# BenchPsu.net
KiCad netlist of a schematic drawn in EAGLE
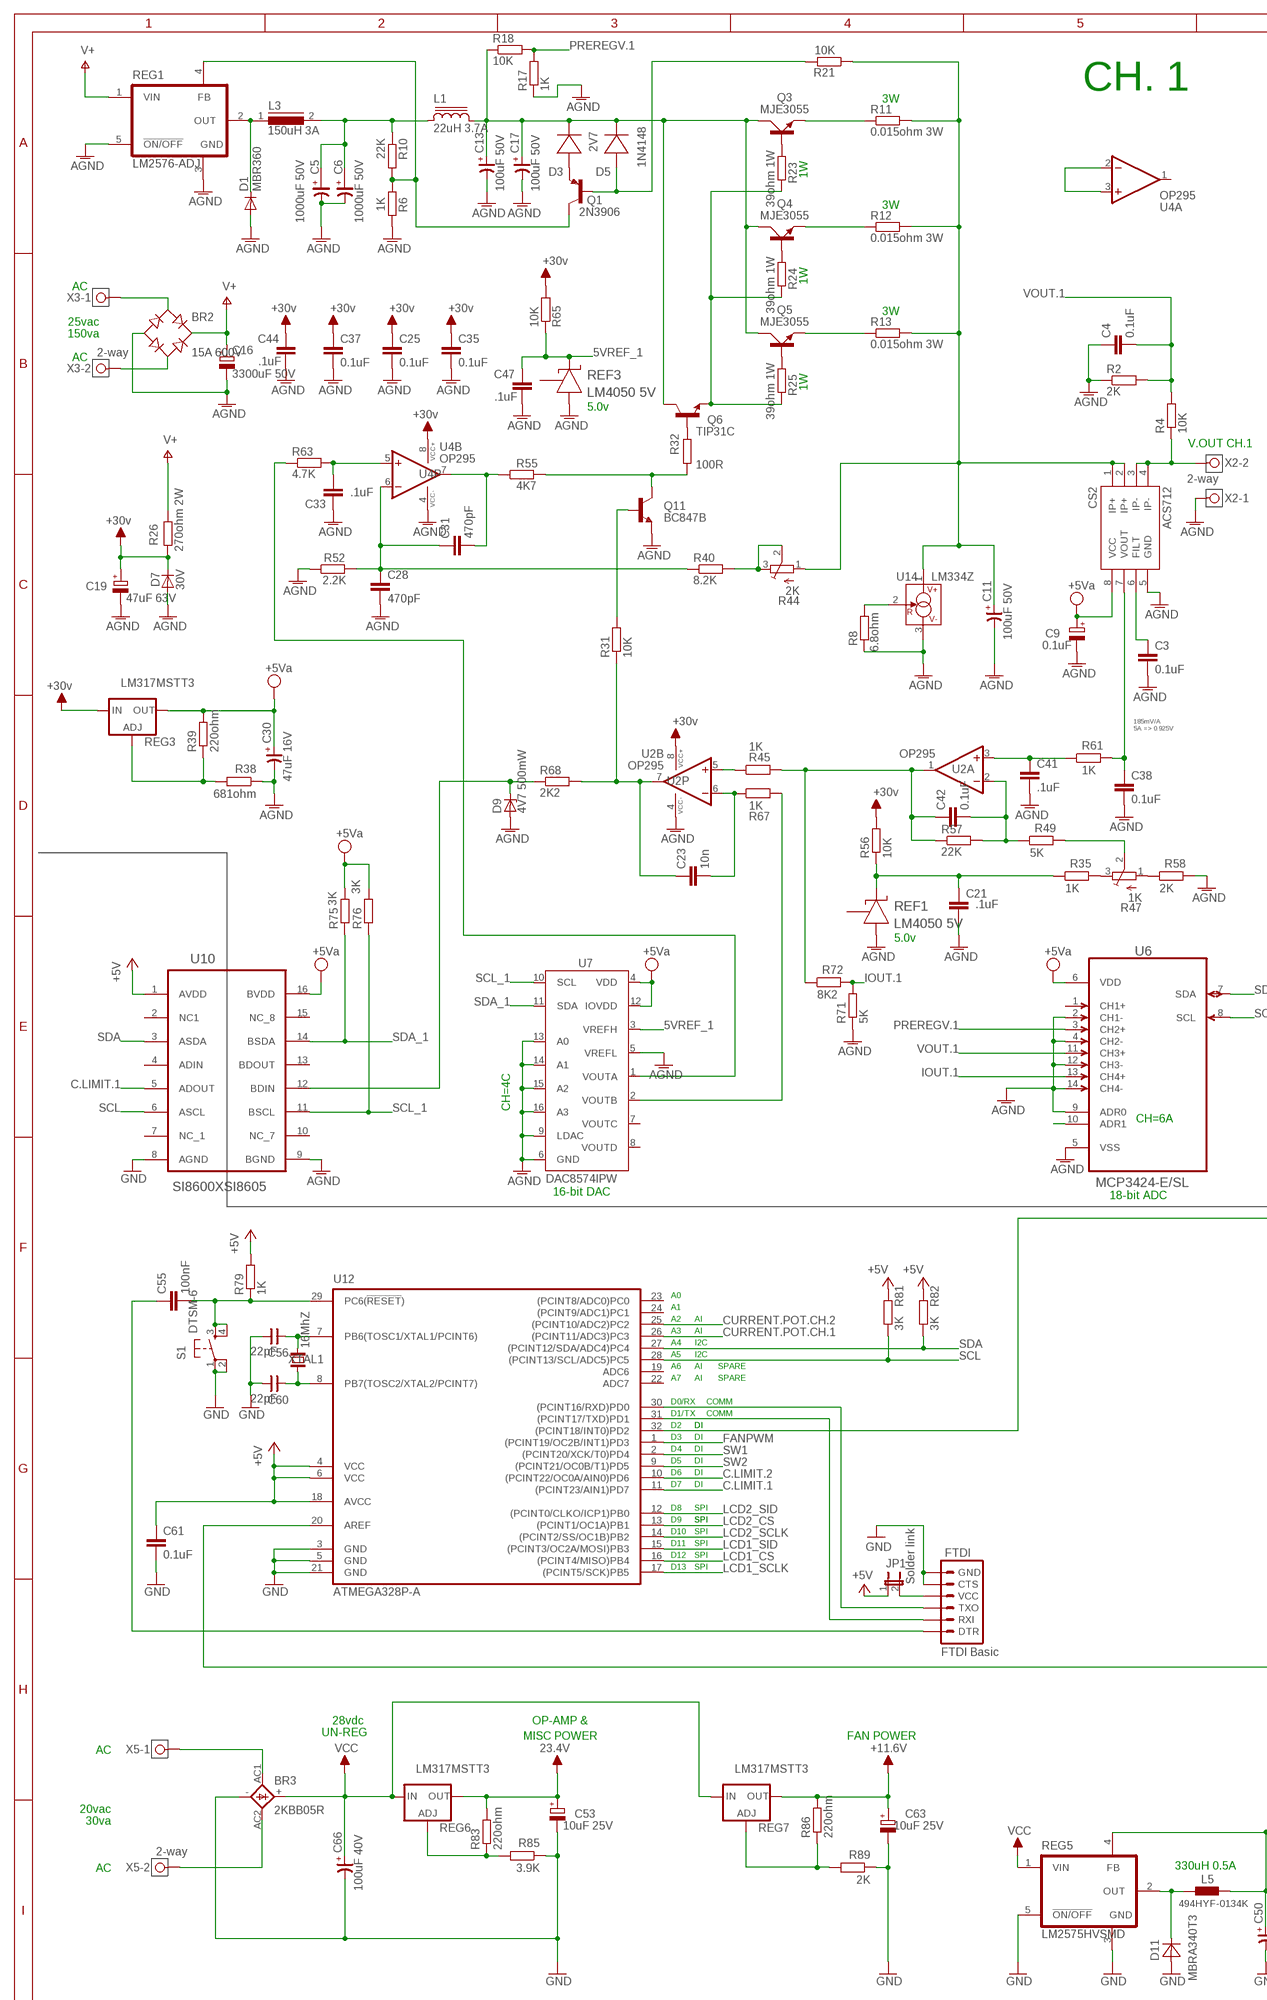
[diagram p0: schematic, sheet 1, part 1 of 2]
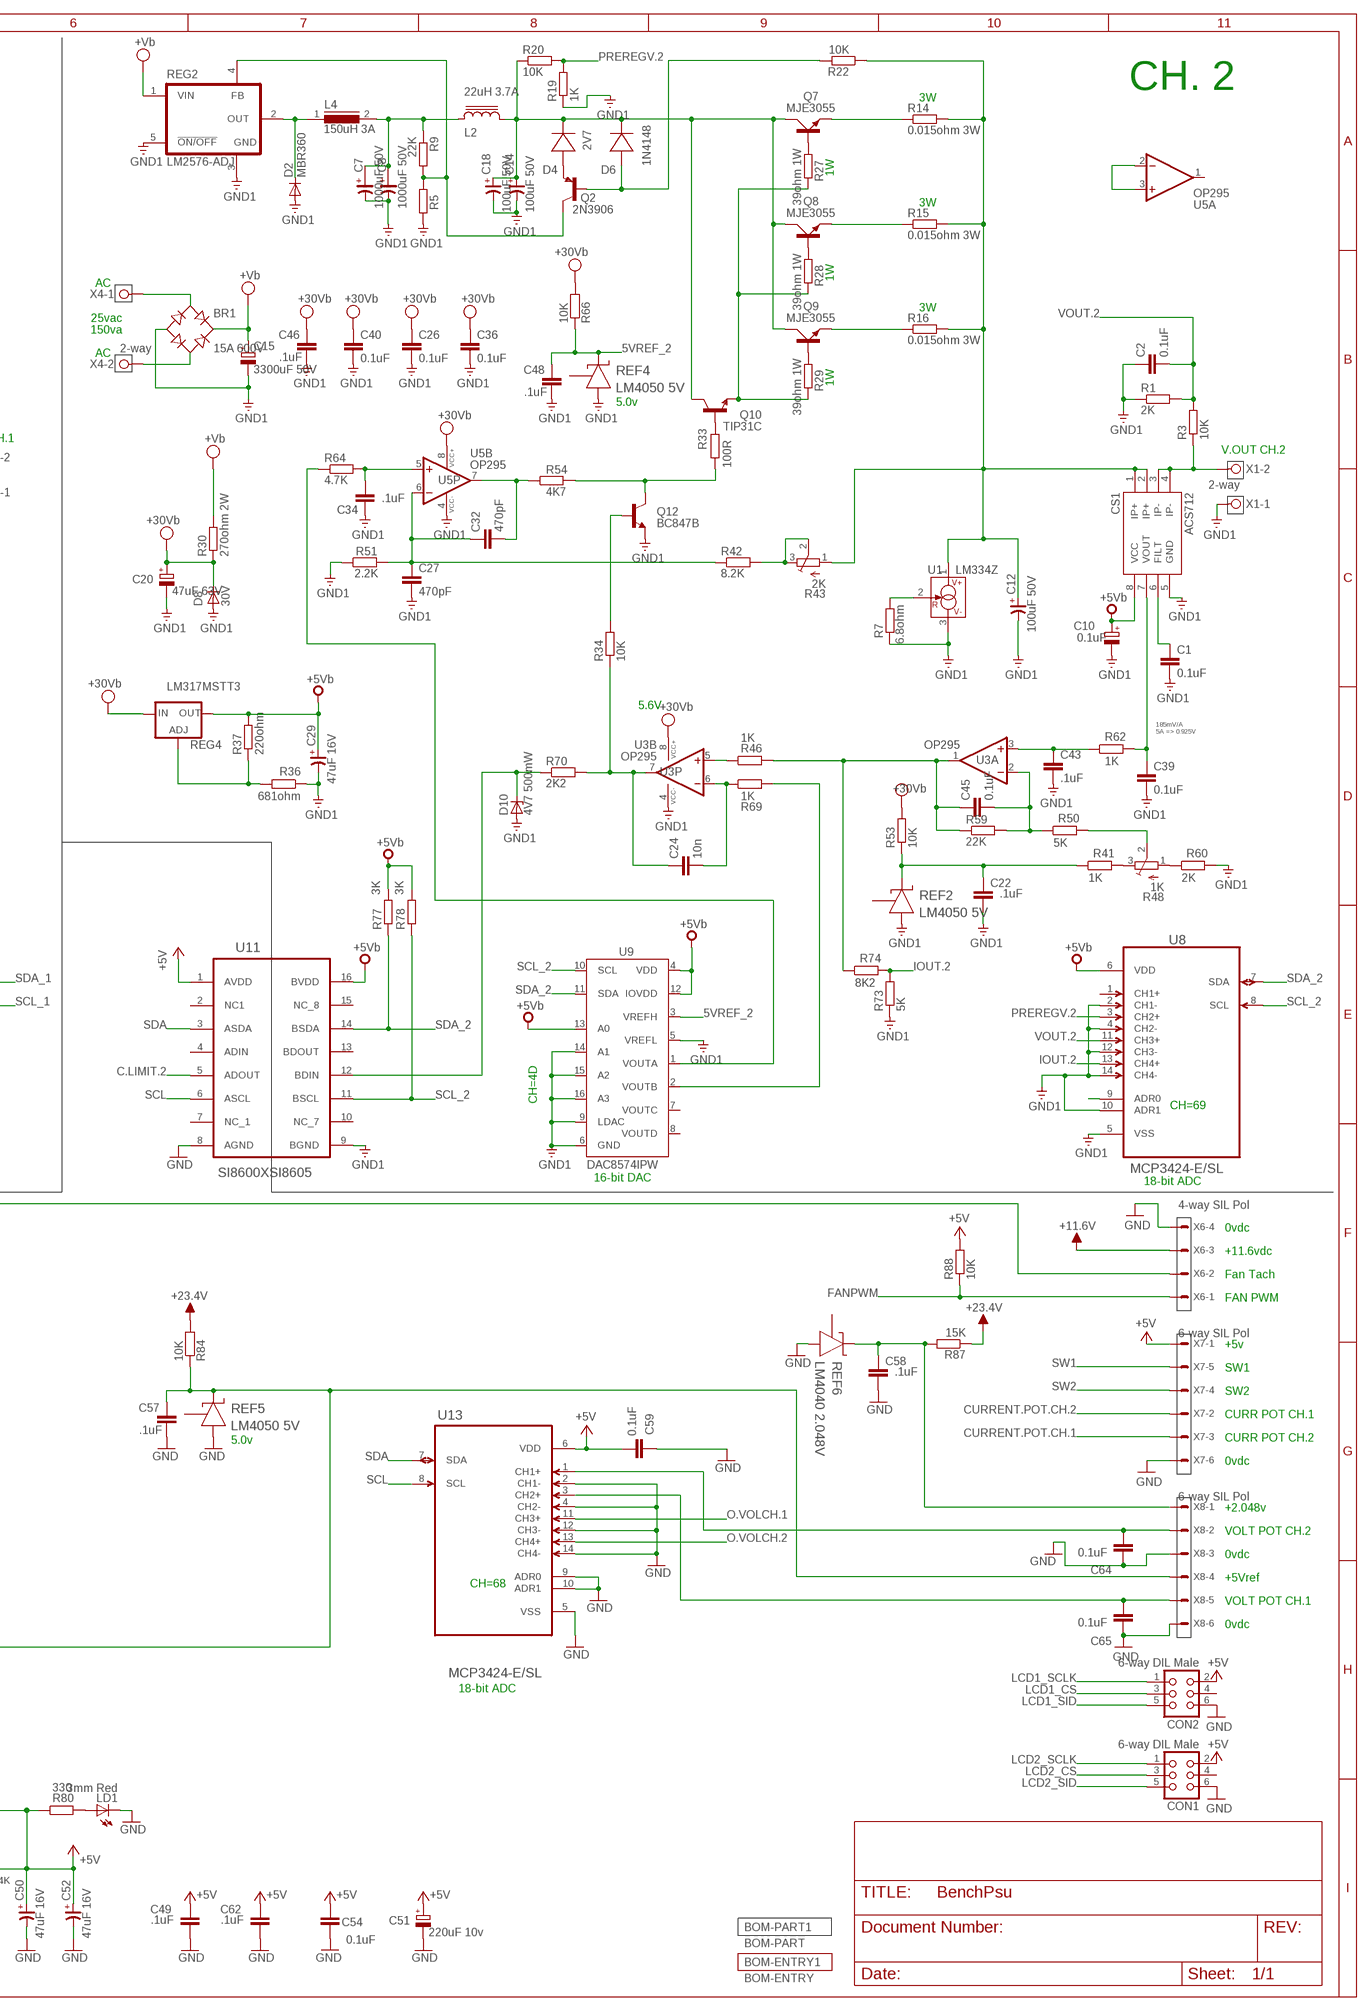
[diagram p1: schematic, sheet 1, part 2 of 2]

(export (version "E")
  (design (tool "Eeschema 10.0.6"))
  (components
    (comp (ref "BR1")
      (value "15A 600V")
      (footprint "eagle-import:GSIB_15A")
      (libsource (lib "eagle-import") (part "GSIB_15A"))
    )
    (comp (ref "BR2")
      (value "15A 600V")
      (footprint "eagle-import:GSIB_15A")
      (libsource (lib "eagle-import") (part "GSIB_15A"))
    )
    (comp (ref "BR3")
      (value "2KBB05R")
      (footprint "eagle-import:2KBB-R")
      (fields (field (name "PARTNO") "RS 700-5330"))
      (libsource (lib "eagle-import") (part "2KBB-R"))
    )
    (comp (ref "C1")
      (value "0.1uF")
      (footprint "eagle-import:C0805")
      (libsource (lib "eagle-import") (part "C-EUC0805"))
    )
    (comp (ref "C2")
      (value "0.1uF")
      (footprint "eagle-import:C0805")
      (libsource (lib "eagle-import") (part "C-EUC0805"))
    )
    (comp (ref "C3")
      (value "0.1uF")
      (footprint "eagle-import:C0805")
      (libsource (lib "eagle-import") (part "C-EUC0805"))
    )
    (comp (ref "C4")
      (value "0.1uF")
      (footprint "eagle-import:C0805")
      (libsource (lib "eagle-import") (part "C-EUC0805"))
    )
    (comp (ref "C5")
      (value "1000uF 50V")
      (footprint "eagle-import:E5,0-12")
      (libsource (lib "eagle-import") (part "C-PRE5,0-12"))
    )
    (comp (ref "C6")
      (value "1000uF 50V")
      (footprint "eagle-import:E5,0-12")
      (libsource (lib "eagle-import") (part "C-PRE5,0-12"))
    )
    (comp (ref "C7")
      (value "1000uF 50V")
      (footprint "eagle-import:E5,0-12")
      (libsource (lib "eagle-import") (part "C-PRE5,0-12"))
    )
    (comp (ref "C8")
      (value "1000uF 50V")
      (footprint "eagle-import:E5,0-12")
      (libsource (lib "eagle-import") (part "C-PRE5,0-12"))
    )
    (comp (ref "C9")
      (value "0.1uF")
      (footprint "eagle-import:E2-5")
      (libsource (lib "eagle-import") (part "CPOL-EUE2-5"))
    )
    (comp (ref "C10")
      (value "0.1uF")
      (footprint "eagle-import:E2-5")
      (libsource (lib "eagle-import") (part "CPOL-EUE2-5"))
    )
    (comp (ref "C11")
      (value "100uF 50V")
      (footprint "eagle-import:E-050X125")
      (fields (field (name "PARTNO") "RS 365-4329"))
      (libsource (lib "eagle-import") (part "CP-E-050X125"))
    )
    (comp (ref "C12")
      (value "100uF 50V")
      (footprint "eagle-import:E-050X125")
      (fields (field (name "PARTNO") "RS 365-4329"))
      (libsource (lib "eagle-import") (part "CP-E-050X125"))
    )
    (comp (ref "C13")
      (value "100uF 50V")
      (footprint "eagle-import:E-035X080")
      (fields (field (name "PARTNO") "RS 737-4421"))
      (libsource (lib "eagle-import") (part "CP-E-035X080"))
    )
    (comp (ref "C14")
      (value "100uF 50V")
      (footprint "eagle-import:E-035X080")
      (fields (field (name "PARTNO") "RS 737-4421"))
      (libsource (lib "eagle-import") (part "CP-E-035X080"))
    )
    (comp (ref "C15")
      (value "3300uF 50V")
      (footprint "eagle-import:E7,5-18")
      (fields (field (name "PARTNO") "RS 684-2030"))
      (libsource (lib "eagle-import") (part "CPOL-EUE7.5-18"))
    )
    (comp (ref "C16")
      (value "3300uF 50V")
      (footprint "eagle-import:E7,5-18")
      (fields (field (name "PARTNO") "RS 684-2030"))
      (libsource (lib "eagle-import") (part "CPOL-EUE7.5-18"))
    )
    (comp (ref "C17")
      (value "100uF 50V")
      (footprint "eagle-import:E-035X080")
      (fields (field (name "PARTNO") "RS 737-4421"))
      (libsource (lib "eagle-import") (part "CP-E-035X080"))
    )
    (comp (ref "C18")
      (value "100uF 50V")
      (footprint "eagle-import:E-035X080")
      (fields (field (name "PARTNO") "RS 737-4421"))
      (libsource (lib "eagle-import") (part "CP-E-035X080"))
    )
    (comp (ref "C19")
      (value "47uF 63V")
      (footprint "eagle-import:E2,5-7")
      (fields (field (name "PARTNO") "IanJ Stock"))
      (libsource (lib "eagle-import") (part "CPOL-EUE2.5-7"))
    )
    (comp (ref "C20")
      (value "47uF 63V")
      (footprint "eagle-import:E2,5-7")
      (fields (field (name "PARTNO") "IanJ stock"))
      (libsource (lib "eagle-import") (part "CPOL-EUE2.5-7"))
    )
    (comp (ref "C21")
      (value ".1uF")
      (footprint "eagle-import:C0805")
      (libsource (lib "eagle-import") (part "C-EUC0805"))
    )
    (comp (ref "C22")
      (value ".1uF")
      (footprint "eagle-import:C0805")
      (libsource (lib "eagle-import") (part "C-EUC0805"))
    )
    (comp (ref "C23")
      (value "10n")
      (footprint "eagle-import:C0805")
      (libsource (lib "eagle-import") (part "C-EUC0805"))
    )
    (comp (ref "C24")
      (value "10n")
      (footprint "eagle-import:C0805")
      (libsource (lib "eagle-import") (part "C-EUC0805"))
    )
    (comp (ref "C25")
      (value "0.1uF")
      (footprint "eagle-import:C0805")
      (libsource (lib "eagle-import") (part "C-EUC0805"))
    )
    (comp (ref "C26")
      (value "0.1uF")
      (footprint "eagle-import:C0805")
      (libsource (lib "eagle-import") (part "C-EUC0805"))
    )
    (comp (ref "C27")
      (value "470pF")
      (footprint "eagle-import:C0805")
      (libsource (lib "eagle-import") (part "C-EUC0805"))
    )
    (comp (ref "C28")
      (value "470pF")
      (footprint "eagle-import:C0805")
      (libsource (lib "eagle-import") (part "C-EUC0805"))
    )
    (comp (ref "C29")
      (value "47uF 16V")
      (footprint "eagle-import:SV-C")
      (libsource (lib "eagle-import") (part "CP-SV-C"))
    )
    (comp (ref "C30")
      (value "47uF 16V")
      (footprint "eagle-import:SV-C")
      (libsource (lib "eagle-import") (part "CP-SV-C"))
    )
    (comp (ref "C31")
      (value "470pF")
      (footprint "eagle-import:C0805")
      (libsource (lib "eagle-import") (part "C-EUC0805"))
    )
    (comp (ref "C32")
      (value "470pF")
      (footprint "eagle-import:C0805")
      (libsource (lib "eagle-import") (part "C-EUC0805"))
    )
    (comp (ref "C33")
      (value ".1uF")
      (footprint "eagle-import:C0805")
      (libsource (lib "eagle-import") (part "C-EUC0805"))
    )
    (comp (ref "C34")
      (value ".1uF")
      (footprint "eagle-import:C0805")
      (libsource (lib "eagle-import") (part "C-EUC0805"))
    )
    (comp (ref "C35")
      (value "0.1uF")
      (footprint "eagle-import:C0805")
      (libsource (lib "eagle-import") (part "C-EUC0805"))
    )
    (comp (ref "C36")
      (value "0.1uF")
      (footprint "eagle-import:C0805")
      (libsource (lib "eagle-import") (part "C-EUC0805"))
    )
    (comp (ref "C37")
      (value "0.1uF")
      (footprint "eagle-import:C0805")
      (libsource (lib "eagle-import") (part "C-EUC0805"))
    )
    (comp (ref "C38")
      (value "0.1uF")
      (footprint "eagle-import:C0805")
      (libsource (lib "eagle-import") (part "C-EUC0805"))
    )
    (comp (ref "C39")
      (value "0.1uF")
      (footprint "eagle-import:C0805")
      (libsource (lib "eagle-import") (part "C-EUC0805"))
    )
    (comp (ref "C40")
      (value "0.1uF")
      (footprint "eagle-import:C0805")
      (libsource (lib "eagle-import") (part "C-EUC0805"))
    )
    (comp (ref "C41")
      (value ".1uF")
      (footprint "eagle-import:C0805")
      (libsource (lib "eagle-import") (part "C-EUC0805"))
    )
    (comp (ref "C42")
      (value "0.1uF")
      (footprint "eagle-import:C0805")
      (libsource (lib "eagle-import") (part "C-EUC0805"))
    )
    (comp (ref "C43")
      (value ".1uF")
      (footprint "eagle-import:C0805")
      (libsource (lib "eagle-import") (part "C-EUC0805"))
    )
    (comp (ref "C44")
      (value ".1uF")
      (footprint "eagle-import:C0805")
      (libsource (lib "eagle-import") (part "C-EUC0805"))
    )
    (comp (ref "C45")
      (value "0.1uF")
      (footprint "eagle-import:C0805")
      (libsource (lib "eagle-import") (part "C-EUC0805"))
    )
    (comp (ref "C46")
      (value ".1uF")
      (footprint "eagle-import:C0805")
      (libsource (lib "eagle-import") (part "C-EUC0805"))
    )
    (comp (ref "C47")
      (value ".1uF")
      (footprint "eagle-import:C0805")
      (libsource (lib "eagle-import") (part "C-EUC0805"))
    )
    (comp (ref "C48")
      (value ".1uF")
      (footprint "eagle-import:C0805")
      (libsource (lib "eagle-import") (part "C-EUC0805"))
    )
    (comp (ref "C49")
      (value ".1uF")
      (footprint "eagle-import:C0805")
      (libsource (lib "eagle-import") (part "C-EUC0805"))
    )
    (comp (ref "C50")
      (value "47uF 16V")
      (footprint "eagle-import:SV-C")
      (libsource (lib "eagle-import") (part "CP-SV-C"))
    )
    (comp (ref "C51")
      (value "220uF 10v")
      (footprint "eagle-import:E2-5")
      (libsource (lib "eagle-import") (part "CPOL-EUE2-5"))
    )
    (comp (ref "C52")
      (value "47uF 16V")
      (footprint "eagle-import:SV-C")
      (libsource (lib "eagle-import") (part "CP-SV-C"))
    )
    (comp (ref "C53")
      (value "10uF 25V")
      (footprint "eagle-import:E2-5")
      (libsource (lib "eagle-import") (part "CPOL-EUE2-5"))
    )
    (comp (ref "C54")
      (value "0.1uF")
      (footprint "eagle-import:C0805")
      (libsource (lib "eagle-import") (part "C-EUC0805"))
    )
    (comp (ref "C55")
      (value "100nF")
      (footprint "eagle-import:C0805")
      (libsource (lib "eagle-import") (part "C-EUC0805"))
    )
    (comp (ref "C56")
      (value "22pF")
      (footprint "eagle-import:ENP-015-040")
      (fields (field (name "PARTNO") "Through hole"))
      (libsource (lib "eagle-import") (part "CBP-ENP-015-040"))
    )
    (comp (ref "C57")
      (value ".1uF")
      (footprint "eagle-import:C0805")
      (libsource (lib "eagle-import") (part "C-EUC0805"))
    )
    (comp (ref "C58")
      (value ".1uF")
      (footprint "eagle-import:C0805")
      (libsource (lib "eagle-import") (part "C-EUC0805"))
    )
    (comp (ref "C59")
      (value "0.1uF")
      (footprint "eagle-import:C0805")
      (libsource (lib "eagle-import") (part "C-EUC0805"))
    )
    (comp (ref "C60")
      (value "22pF")
      (footprint "eagle-import:ENP-015-040")
      (fields (field (name "PARTNO") "Through hole"))
      (libsource (lib "eagle-import") (part "CBP-ENP-015-040"))
    )
    (comp (ref "C61")
      (value "0.1uF")
      (footprint "eagle-import:C0805")
      (libsource (lib "eagle-import") (part "C-EUC0805"))
    )
    (comp (ref "C62")
      (value ".1uF")
      (footprint "eagle-import:C0805")
      (libsource (lib "eagle-import") (part "C-EUC0805"))
    )
    (comp (ref "C63")
      (value "10uF 25V")
      (footprint "eagle-import:E2-5")
      (libsource (lib "eagle-import") (part "CPOL-EUE2-5"))
    )
    (comp (ref "C64")
      (value "0.1uF")
      (footprint "eagle-import:C0805")
      (libsource (lib "eagle-import") (part "C-EUC0805"))
    )
    (comp (ref "C65")
      (value "0.1uF")
      (footprint "eagle-import:C0805")
      (libsource (lib "eagle-import") (part "C-EUC0805"))
    )
    (comp (ref "C66")
      (value "100uF 40V")
      (footprint "eagle-import:SV-E_F")
      (libsource (lib "eagle-import") (part "CP-SV-E/F"))
    )
    (comp (ref "CON1")
      (value "6-way DIL Male")
      (footprint "eagle-import:CON06")
      (libsource (lib "eagle-import") (part "CON06"))
    )
    (comp (ref "CON2")
      (value "6-way DIL Male")
      (footprint "eagle-import:CON06")
      (libsource (lib "eagle-import") (part "CON06"))
    )
    (comp (ref "CS1")
      (value "ACS712")
      (footprint "eagle-import:SO08")
      (libsource (lib "eagle-import") (part "ACS712"))
    )
    (comp (ref "CS2")
      (value "ACS712")
      (footprint "eagle-import:SO08")
      (libsource (lib "eagle-import") (part "ACS712"))
    )
    (comp (ref "D1")
      (value "MBR360")
      (footprint "eagle-import:DO-201-15_V")
      (libsource (lib "eagle-import") (part "1N5400VERTICAL"))
    )
    (comp (ref "D2")
      (value "MBR360")
      (footprint "eagle-import:DO-201-15_V")
      (libsource (lib "eagle-import") (part "1N5400VERTICAL"))
    )
    (comp (ref "D3")
      (value "2V7")
      (footprint "eagle-import:SOD123")
      (libsource (lib "eagle-import") (part "DIODE"))
    )
    (comp (ref "D4")
      (value "2V7")
      (footprint "eagle-import:SOD123")
      (libsource (lib "eagle-import") (part "DIODE"))
    )
    (comp (ref "D5")
      (value "1N4148")
      (footprint "eagle-import:SOD123")
      (libsource (lib "eagle-import") (part "DIODE"))
    )
    (comp (ref "D6")
      (value "1N4148")
      (footprint "eagle-import:SOD123")
      (libsource (lib "eagle-import") (part "DIODE"))
    )
    (comp (ref "D7")
      (value "30V")
      (footprint "eagle-import:D015-12_V")
      (libsource (lib "eagle-import") (part "1N5060GPVERTICAL"))
    )
    (comp (ref "D8")
      (value "30V")
      (footprint "eagle-import:D015-12_V")
      (libsource (lib "eagle-import") (part "1N5060GPVERTICAL"))
    )
    (comp (ref "D9")
      (value "4V7 500mW")
      (footprint "eagle-import:SOD80C")
      (libsource (lib "eagle-import") (part "ZENER-DIODESOD80C"))
    )
    (comp (ref "D10")
      (value "4V7 500mW")
      (footprint "eagle-import:SOD80C")
      (libsource (lib "eagle-import") (part "ZENER-DIODESOD80C"))
    )
    (comp (ref "D11")
      (value "MBRA340T3")
      (footprint "eagle-import:SMA")
      (libsource (lib "eagle-import") (part "MBRA340T3"))
    )
    (comp (ref "FTDI")
      (value "FTDI Basic")
      (footprint "eagle-import:1X06")
      (libsource (lib "eagle-import") (part "ARDUINO_SERIAL_PROGRAMPTH"))
    )
    (comp (ref "JP1")
      (value "Solder link")
      (footprint "eagle-import:JP1")
      (libsource (lib "eagle-import") (part "JP1E"))
    )
    (comp (ref "L1")
      (value "22uH 3.7A")
      (footprint "eagle-import:RS749-8366_THT22UH")
      (fields (field (name "PARTNO") "RS 749-8366"))
      (libsource (lib "eagle-import") (part "L-"))
    )
    (comp (ref "L2")
      (value "22uH 3.7A")
      (footprint "eagle-import:RS749-8366_THT22UH")
      (fields (field (name "PARTNO") "RS 749-8366"))
      (libsource (lib "eagle-import") (part "L-"))
    )
    (comp (ref "L3")
      (value "150uH 3A")
      (footprint "eagle-import:SFT1030")
      (fields (field (name "PARTNO") "RS 742-7991"))
      (libsource (lib "eagle-import") (part "SFT1030"))
    )
    (comp (ref "L4")
      (value "150uH 3A")
      (footprint "eagle-import:SFT1030")
      (fields (field (name "PARTNO") "RS 742-7991"))
      (libsource (lib "eagle-import") (part "SFT1030"))
    )
    (comp (ref "L5")
      (value "494HYF-0134K")
      (footprint "eagle-import:0.2PIN_0.3DIA")
      (libsource (lib "eagle-import") (part "494HYF-0134K"))
    )
    (comp (ref "LD1")
      (value "3mm Red")
      (footprint "eagle-import:LED3MM")
      (libsource (lib "eagle-import") (part "LED3MM"))
    )
    (comp (ref "Q1")
      (value "2N3906")
      (footprint "eagle-import:SOT23-BEC")
      (libsource (lib "eagle-import") (part "BC327SMD"))
    )
    (comp (ref "Q2")
      (value "2N3906")
      (footprint "eagle-import:SOT23-BEC")
      (libsource (lib "eagle-import") (part "BC327SMD"))
    )
    (comp (ref "Q3")
      (value "MJE3055")
      (footprint "eagle-import:TO220AV")
      (libsource (lib "eagle-import") (part "MJE3055"))
    )
    (comp (ref "Q4")
      (value "MJE3055")
      (footprint "eagle-import:TO220AV")
      (libsource (lib "eagle-import") (part "MJE3055"))
    )
    (comp (ref "Q5")
      (value "MJE3055")
      (footprint "eagle-import:TO220AV")
      (libsource (lib "eagle-import") (part "MJE3055"))
    )
    (comp (ref "Q6")
      (value "TIP31C")
      (footprint "eagle-import:TO220V")
      (libsource (lib "eagle-import") (part "TIP31CVERTICAL"))
    )
    (comp (ref "Q7")
      (value "MJE3055")
      (footprint "eagle-import:TO220AV")
      (libsource (lib "eagle-import") (part "MJE3055"))
    )
    (comp (ref "Q8")
      (value "MJE3055")
      (footprint "eagle-import:TO220AV")
      (libsource (lib "eagle-import") (part "MJE3055"))
    )
    (comp (ref "Q9")
      (value "MJE3055")
      (footprint "eagle-import:TO220AV")
      (libsource (lib "eagle-import") (part "MJE3055"))
    )
    (comp (ref "Q10")
      (value "TIP31C")
      (footprint "eagle-import:TO220V")
      (libsource (lib "eagle-import") (part "TIP31CVERTICAL"))
    )
    (comp (ref "Q11")
      (value "BC847B")
      (footprint "eagle-import:SOT23")
      (libsource (lib "eagle-import") (part "BC847SMDB"))
    )
    (comp (ref "Q12")
      (value "BC847B")
      (footprint "eagle-import:SOT23")
      (libsource (lib "eagle-import") (part "BC847SMDB"))
    )
    (comp (ref "R1")
      (value "2K")
      (footprint "eagle-import:R0805")
      (libsource (lib "eagle-import") (part "R-EU_R0805"))
    )
    (comp (ref "R2")
      (value "2K")
      (footprint "eagle-import:R0805")
      (libsource (lib "eagle-import") (part "R-EU_R0805"))
    )
    (comp (ref "R3")
      (value "10K")
      (footprint "eagle-import:R0805")
      (libsource (lib "eagle-import") (part "R-EU_R0805"))
    )
    (comp (ref "R4")
      (value "10K")
      (footprint "eagle-import:R0805")
      (libsource (lib "eagle-import") (part "R-EU_R0805"))
    )
    (comp (ref "R5")
      (value "1K")
      (footprint "eagle-import:R0805")
      (libsource (lib "eagle-import") (part "R-EU_R0805"))
    )
    (comp (ref "R6")
      (value "1K")
      (footprint "eagle-import:R0805")
      (libsource (lib "eagle-import") (part "R-EU_R0805"))
    )
    (comp (ref "R7")
      (value "6.8ohm")
      (footprint "eagle-import:R0805")
      (libsource (lib "eagle-import") (part "R-EU_R0805"))
    )
    (comp (ref "R8")
      (value "6.8ohm")
      (footprint "eagle-import:R0805")
      (libsource (lib "eagle-import") (part "R-EU_R0805"))
    )
    (comp (ref "R9")
      (value "22K")
      (footprint "eagle-import:R0805")
      (libsource (lib "eagle-import") (part "R-EU_R0805"))
    )
    (comp (ref "R10")
      (value "22K")
      (footprint "eagle-import:R0805")
      (libsource (lib "eagle-import") (part "R-EU_R0805"))
    )
    (comp (ref "R11")
      (value "0.015ohm 3W")
      (footprint "eagle-import:R2512")
      (fields (field (name "PARTNO") "RS 720-3164"))
      (libsource (lib "eagle-import") (part "R-EU_R2512"))
    )
    (comp (ref "R12")
      (value "0.015ohm 3W")
      (footprint "eagle-import:R2512")
      (fields (field (name "PARTNO") "RS 720-3164"))
      (libsource (lib "eagle-import") (part "R-EU_R2512"))
    )
    (comp (ref "R13")
      (value "0.015ohm 3W")
      (footprint "eagle-import:R2512")
      (fields (field (name "PARTNO") "RS 720-3164"))
      (libsource (lib "eagle-import") (part "R-EU_R2512"))
    )
    (comp (ref "R14")
      (value "0.015ohm 3W")
      (footprint "eagle-import:R2512")
      (fields (field (name "PARTNO") "RS 720-3164"))
      (libsource (lib "eagle-import") (part "R-EU_R2512"))
    )
    (comp (ref "R15")
      (value "0.015ohm 3W")
      (footprint "eagle-import:R2512")
      (fields (field (name "PARTNO") "RS 720-3164"))
      (libsource (lib "eagle-import") (part "R-EU_R2512"))
    )
    (comp (ref "R16")
      (value "0.015ohm 3W")
      (footprint "eagle-import:R2512")
      (fields (field (name "PARTNO") "RS 720-3164"))
      (libsource (lib "eagle-import") (part "R-EU_R2512"))
    )
    (comp (ref "R17")
      (value "1K")
      (footprint "eagle-import:R0805")
      (libsource (lib "eagle-import") (part "R-EU_R0805"))
    )
    (comp (ref "R18")
      (value "10K")
      (footprint "eagle-import:R0805")
      (libsource (lib "eagle-import") (part "R-EU_R0805"))
    )
    (comp (ref "R19")
      (value "1K")
      (footprint "eagle-import:R0805")
      (libsource (lib "eagle-import") (part "R-EU_R0805"))
    )
    (comp (ref "R20")
      (value "10K")
      (footprint "eagle-import:R0805")
      (libsource (lib "eagle-import") (part "R-EU_R0805"))
    )
    (comp (ref "R21")
      (value "10K")
      (footprint "eagle-import:R0805")
      (libsource (lib "eagle-import") (part "R-EU_R0805"))
    )
    (comp (ref "R22")
      (value "10K")
      (footprint "eagle-import:R0805")
      (libsource (lib "eagle-import") (part "R-EU_R0805"))
    )
    (comp (ref "R23")
      (value "39ohm 1W")
      (footprint "eagle-import:0411V")
      (libsource (lib "eagle-import") (part "R-EU_0411/3V"))
    )
    (comp (ref "R24")
      (value "39ohm 1W")
      (footprint "eagle-import:0411V")
      (libsource (lib "eagle-import") (part "R-EU_0411/3V"))
    )
    (comp (ref "R25")
      (value "39ohm 1W")
      (footprint "eagle-import:0411V")
      (libsource (lib "eagle-import") (part "R-EU_0411/3V"))
    )
    (comp (ref "R26")
      (value "270ohm 2W")
      (footprint "eagle-import:P0613V")
      (libsource (lib "eagle-import") (part "R-EU_0613/5V"))
    )
    (comp (ref "R27")
      (value "39ohm 1W")
      (footprint "eagle-import:0411V")
      (libsource (lib "eagle-import") (part "R-EU_0411/3V"))
    )
    (comp (ref "R28")
      (value "39ohm 1W")
      (footprint "eagle-import:0411V")
      (libsource (lib "eagle-import") (part "R-EU_0411/3V"))
    )
    (comp (ref "R29")
      (value "39ohm 1W")
      (footprint "eagle-import:0411V")
      (libsource (lib "eagle-import") (part "R-EU_0411/3V"))
    )
    (comp (ref "R30")
      (value "270ohm 2W")
      (footprint "eagle-import:P0613V")
      (libsource (lib "eagle-import") (part "R-EU_0613/5V"))
    )
    (comp (ref "R31")
      (value "10K")
      (footprint "eagle-import:R0805")
      (libsource (lib "eagle-import") (part "R-EU_R0805"))
    )
    (comp (ref "R32")
      (value "100R")
      (footprint "eagle-import:R0805")
      (libsource (lib "eagle-import") (part "R-EU_R0805"))
    )
    (comp (ref "R33")
      (value "100R")
      (footprint "eagle-import:R0805")
      (libsource (lib "eagle-import") (part "R-EU_R0805"))
    )
    (comp (ref "R34")
      (value "10K")
      (footprint "eagle-import:R0805")
      (libsource (lib "eagle-import") (part "R-EU_R0805"))
    )
    (comp (ref "R35")
      (value "1K")
      (footprint "eagle-import:R0805")
      (libsource (lib "eagle-import") (part "R-EU_R0805"))
    )
    (comp (ref "R36")
      (value "681ohm")
      (footprint "eagle-import:R0805")
      (libsource (lib "eagle-import") (part "R-EU_R0805"))
    )
    (comp (ref "R37")
      (value "220ohm")
      (footprint "eagle-import:R0805")
      (libsource (lib "eagle-import") (part "R-EU_R0805"))
    )
    (comp (ref "R38")
      (value "681ohm")
      (footprint "eagle-import:R0805")
      (libsource (lib "eagle-import") (part "R-EU_R0805"))
    )
    (comp (ref "R39")
      (value "220ohm")
      (footprint "eagle-import:R0805")
      (libsource (lib "eagle-import") (part "R-EU_R0805"))
    )
    (comp (ref "R40")
      (value "8.2K")
      (footprint "eagle-import:R0805")
      (libsource (lib "eagle-import") (part "R-EU_R0805"))
    )
    (comp (ref "R41")
      (value "1K")
      (footprint "eagle-import:R0805")
      (libsource (lib "eagle-import") (part "R-EU_R0805"))
    )
    (comp (ref "R42")
      (value "8.2K")
      (footprint "eagle-import:R0805")
      (libsource (lib "eagle-import") (part "R-EU_R0805"))
    )
    (comp (ref "R43")
      (value "2K")
      (footprint "eagle-import:SM-42_43W")
      (libsource (lib "eagle-import") (part "TRIM_EU-SM-42/43W"))
    )
    (comp (ref "R44")
      (value "2K")
      (footprint "eagle-import:SM-42_43W")
      (libsource (lib "eagle-import") (part "TRIM_EU-SM-42/43W"))
    )
    (comp (ref "R45")
      (value "1K")
      (footprint "eagle-import:R0805")
      (libsource (lib "eagle-import") (part "R-EU_R0805"))
    )
    (comp (ref "R46")
      (value "1K")
      (footprint "eagle-import:R0805")
      (libsource (lib "eagle-import") (part "R-EU_R0805"))
    )
    (comp (ref "R47")
      (value "1K")
      (footprint "eagle-import:3223W")
      (libsource (lib "eagle-import") (part "TRIM_EU-3223W"))
    )
    (comp (ref "R48")
      (value "1K")
      (footprint "eagle-import:SM-42_43W")
      (libsource (lib "eagle-import") (part "TRIM_EU-SM-42/43W"))
    )
    (comp (ref "R49")
      (value "5K")
      (footprint "eagle-import:R0805")
      (libsource (lib "eagle-import") (part "R-EU_R0805"))
    )
    (comp (ref "R50")
      (value "5K")
      (footprint "eagle-import:R0805")
      (libsource (lib "eagle-import") (part "R-EU_R0805"))
    )
    (comp (ref "R51")
      (value "2.2K")
      (footprint "eagle-import:R0805")
      (libsource (lib "eagle-import") (part "R-EU_R0805"))
    )
    (comp (ref "R52")
      (value "2.2K")
      (footprint "eagle-import:R0805")
      (libsource (lib "eagle-import") (part "R-EU_R0805"))
    )
    (comp (ref "R53")
      (value "10K")
      (footprint "eagle-import:R0805")
      (libsource (lib "eagle-import") (part "R-EU_R0805"))
    )
    (comp (ref "R54")
      (value "4K7")
      (footprint "eagle-import:R0805")
      (libsource (lib "eagle-import") (part "R-EU_R0805"))
    )
    (comp (ref "R55")
      (value "4K7")
      (footprint "eagle-import:R0805")
      (libsource (lib "eagle-import") (part "R-EU_R0805"))
    )
    (comp (ref "R56")
      (value "10K")
      (footprint "eagle-import:R0805")
      (libsource (lib "eagle-import") (part "R-EU_R0805"))
    )
    (comp (ref "R57")
      (value "22K")
      (footprint "eagle-import:R0805")
      (libsource (lib "eagle-import") (part "R-EU_R0805"))
    )
    (comp (ref "R58")
      (value "2K")
      (footprint "eagle-import:R0805")
      (libsource (lib "eagle-import") (part "R-EU_R0805"))
    )
    (comp (ref "R59")
      (value "22K")
      (footprint "eagle-import:R0805")
      (libsource (lib "eagle-import") (part "R-EU_R0805"))
    )
    (comp (ref "R60")
      (value "2K")
      (footprint "eagle-import:R0805")
      (libsource (lib "eagle-import") (part "R-EU_R0805"))
    )
    (comp (ref "R61")
      (value "1K")
      (footprint "eagle-import:R0805")
      (libsource (lib "eagle-import") (part "R-EU_R0805"))
    )
    (comp (ref "R62")
      (value "1K")
      (footprint "eagle-import:R0805")
      (libsource (lib "eagle-import") (part "R-EU_R0805"))
    )
    (comp (ref "R63")
      (value "4.7K")
      (footprint "eagle-import:R0805")
      (libsource (lib "eagle-import") (part "R-EU_R0805"))
    )
    (comp (ref "R64")
      (value "4.7K")
      (footprint "eagle-import:R0805")
      (libsource (lib "eagle-import") (part "R-EU_R0805"))
    )
    (comp (ref "R65")
      (value "10K")
      (footprint "eagle-import:R0805")
      (libsource (lib "eagle-import") (part "R-EU_R0805"))
    )
    (comp (ref "R66")
      (value "10K")
      (footprint "eagle-import:R0805")
      (libsource (lib "eagle-import") (part "R-EU_R0805"))
    )
    (comp (ref "R67")
      (value "1K")
      (footprint "eagle-import:R0805")
      (libsource (lib "eagle-import") (part "R-EU_R0805"))
    )
    (comp (ref "R68")
      (value "2K2")
      (footprint "eagle-import:R0805")
      (libsource (lib "eagle-import") (part "R-EU_R0805"))
    )
    (comp (ref "R69")
      (value "1K")
      (footprint "eagle-import:R0805")
      (libsource (lib "eagle-import") (part "R-EU_R0805"))
    )
    (comp (ref "R70")
      (value "2K2")
      (footprint "eagle-import:R0805")
      (libsource (lib "eagle-import") (part "R-EU_R0805"))
    )
    (comp (ref "R71")
      (value "5K")
      (footprint "eagle-import:R0805")
      (libsource (lib "eagle-import") (part "R-EU_R0805"))
    )
    (comp (ref "R72")
      (value "8K2")
      (footprint "eagle-import:R0805")
      (libsource (lib "eagle-import") (part "R-EU_R0805"))
    )
    (comp (ref "R73")
      (value "5K")
      (footprint "eagle-import:R0805")
      (libsource (lib "eagle-import") (part "R-EU_R0805"))
    )
    (comp (ref "R74")
      (value "8K2")
      (footprint "eagle-import:R0805")
      (libsource (lib "eagle-import") (part "R-EU_R0805"))
    )
    (comp (ref "R75")
      (value "3K")
      (footprint "eagle-import:R0805")
      (libsource (lib "eagle-import") (part "R-EU_R0805"))
    )
    (comp (ref "R76")
      (value "3K")
      (footprint "eagle-import:R0805")
      (libsource (lib "eagle-import") (part "R-EU_R0805"))
    )
    (comp (ref "R77")
      (value "3K")
      (footprint "eagle-import:R0805")
      (libsource (lib "eagle-import") (part "R-EU_R0805"))
    )
    (comp (ref "R78")
      (value "3K")
      (footprint "eagle-import:R0805")
      (libsource (lib "eagle-import") (part "R-EU_R0805"))
    )
    (comp (ref "R79")
      (value "1K")
      (footprint "eagle-import:R0805")
      (libsource (lib "eagle-import") (part "R-EU_R0805"))
    )
    (comp (ref "R80")
      (value "330")
      (footprint "eagle-import:R0805")
      (libsource (lib "eagle-import") (part "R-EU_R0805"))
    )
    (comp (ref "R81")
      (value "3K")
      (footprint "eagle-import:R0805")
      (libsource (lib "eagle-import") (part "R-EU_R0805"))
    )
    (comp (ref "R82")
      (value "3K")
      (footprint "eagle-import:R0805")
      (libsource (lib "eagle-import") (part "R-EU_R0805"))
    )
    (comp (ref "R83")
      (value "220ohm")
      (footprint "eagle-import:R0805")
      (libsource (lib "eagle-import") (part "R-EU_R0805"))
    )
    (comp (ref "R84")
      (value "10K")
      (footprint "eagle-import:R0805")
      (libsource (lib "eagle-import") (part "R-EU_R0805"))
    )
    (comp (ref "R85")
      (value "3.9K")
      (footprint "eagle-import:R0805")
      (libsource (lib "eagle-import") (part "R-EU_R0805"))
    )
    (comp (ref "R86")
      (value "220ohm")
      (footprint "eagle-import:R0805")
      (libsource (lib "eagle-import") (part "R-EU_R0805"))
    )
    (comp (ref "R87")
      (value "15K")
      (footprint "eagle-import:R0805")
      (libsource (lib "eagle-import") (part "R-EU_R0805"))
    )
    (comp (ref "R88")
      (value "10K")
      (footprint "eagle-import:R0805")
      (libsource (lib "eagle-import") (part "R-EU_R0805"))
    )
    (comp (ref "R89")
      (value "2K")
      (footprint "eagle-import:R0805")
      (libsource (lib "eagle-import") (part "R-EU_R0805"))
    )
    (comp (ref "REF1")
      (value "LM4050 5V")
      (footprint "eagle-import:SOT95P237X112-3N")
      (fields (field (name "MPN") "LM4040A20IDBZT"))
      (libsource (lib "eagle-import") (part "LM4040A20IDBZT"))
    )
    (comp (ref "REF2")
      (value "LM4050 5V")
      (footprint "eagle-import:SOT95P237X112-3N")
      (fields (field (name "MPN") "LM4040A20IDBZT"))
      (libsource (lib "eagle-import") (part "LM4040A20IDBZT"))
    )
    (comp (ref "REF3")
      (value "LM4050 5V")
      (footprint "eagle-import:SOT95P237X112-3N")
      (fields
        (field (name "MPN") "LM4040A20IDBZT")
        (field (name "MPN_1") "LM4040A20IDBZT")
        (field (name "OC_FARNELL") "1702826")
        (field (name "OC_NEWARK") "53K9321")
        (field (name "PACKAGE") "3-SOT-23")
        (field (name "SUPPLIER") "TEXAS INSTRUMENTS")
      )
      (libsource (lib "eagle-import") (part "LM4040A20IDBZT"))
    )
    (comp (ref "REF4")
      (value "LM4050 5V")
      (footprint "eagle-import:SOT95P237X112-3N")
      (fields
        (field (name "MPN") "LM4040A20IDBZT")
        (field (name "MPN_1") "LM4040A20IDBZT")
        (field (name "OC_FARNELL") "1702826")
        (field (name "OC_NEWARK") "53K9321")
        (field (name "PACKAGE") "3-SOT-23")
        (field (name "SUPPLIER") "TEXAS INSTRUMENTS")
      )
      (libsource (lib "eagle-import") (part "LM4040A20IDBZT"))
    )
    (comp (ref "REF5")
      (value "LM4050 5V")
      (footprint "eagle-import:SOT95P237X112-3N")
      (fields
        (field (name "MPN") "LM4040A20IDBZT")
        (field (name "MPN_1") "LM4040A20IDBZT")
        (field (name "OC_FARNELL") "1702826")
        (field (name "OC_NEWARK") "53K9321")
        (field (name "PACKAGE") "3-SOT-23")
        (field (name "SUPPLIER") "TEXAS INSTRUMENTS")
      )
      (libsource (lib "eagle-import") (part "LM4040A20IDBZT"))
    )
    (comp (ref "REF6")
      (value "LM4040 2.048V")
      (footprint "eagle-import:SOT95P237X112-3N")
      (fields (field (name "MPN") "LM4040A20IDBZT"))
      (libsource (lib "eagle-import") (part "LM4040A20IDBZT"))
    )
    (comp (ref "REG1")
      (value "LM2576-ADJ")
      (footprint "eagle-import:LM2575HV_V_2")
      (libsource (lib "eagle-import") (part "LM2575HV_VVERTICAL_2"))
    )
    (comp (ref "REG2")
      (value "LM2576-ADJ")
      (footprint "eagle-import:LM2575HV_V_2")
      (libsource (lib "eagle-import") (part "LM2575HV_VVERTICAL_2"))
    )
    (comp (ref "REG3")
      (value "LM317MSTT3")
      (footprint "eagle-import:SOT223")
      (libsource (lib "eagle-import") (part "LM317?MSTT3"))
    )
    (comp (ref "REG4")
      (value "LM317MSTT3")
      (footprint "eagle-import:SOT223")
      (libsource (lib "eagle-import") (part "LM317?MSTT3"))
    )
    (comp (ref "REG5")
      (value "LM2575HVSMD")
      (footprint "eagle-import:TO263-5")
      (libsource (lib "eagle-import") (part "LM2575HVSMD"))
    )
    (comp (ref "REG6")
      (value "LM317MSTT3")
      (footprint "eagle-import:SOT223")
      (libsource (lib "eagle-import") (part "LM317?MSTT3"))
    )
    (comp (ref "REG7")
      (value "LM317MSTT3")
      (footprint "eagle-import:SOT223")
      (libsource (lib "eagle-import") (part "LM317?MSTT3"))
    )
    (comp (ref "S1")
      (value "DTSM-6")
      (footprint "eagle-import:DTSM-6")
      (libsource (lib "eagle-import") (part "DTSM-6"))
    )
    (comp (ref "U1")
      (value "LM334Z")
      (footprint "eagle-import:TO92")
      (libsource (lib "eagle-import") (part "LM34Z3"))
    )
    (comp (ref "U2")
      (value "OP295")
      (footprint "eagle-import:SO08")
      (libsource (lib "eagle-import") (part "TL072N"))
    )
    (comp (ref "U3")
      (value "OP295")
      (footprint "eagle-import:SO08")
      (libsource (lib "eagle-import") (part "TL072N"))
    )
    (comp (ref "U4")
      (value "OP295")
      (footprint "eagle-import:SO08")
      (libsource (lib "eagle-import") (part "TL072N"))
    )
    (comp (ref "U5")
      (value "OP295")
      (footprint "eagle-import:SO08")
      (libsource (lib "eagle-import") (part "TL072N"))
    )
    (comp (ref "U6")
      (value "MCP3424-E/SL")
      (footprint "eagle-import:SOIC127P600X175-14N")
      (libsource (lib "eagle-import") (part "MCP3424-E/SL"))
    )
    (comp (ref "U7")
      (value "DAC8574IPW")
      (footprint "eagle-import:TSSOP16")
      (libsource (lib "eagle-import") (part "DAC8574IPW"))
    )
    (comp (ref "U8")
      (value "MCP3424-E/SL")
      (footprint "eagle-import:SOIC127P600X175-14N")
      (libsource (lib "eagle-import") (part "MCP3424-E/SL"))
    )
    (comp (ref "U9")
      (value "DAC8574IPW")
      (footprint "eagle-import:TSSOP16")
      (libsource (lib "eagle-import") (part "DAC8574IPW"))
    )
    (comp (ref "U10")
      (value "SI8600XSI8605")
      (footprint "eagle-import:SOIC16N")
      (libsource (lib "eagle-import") (part "SI8600XSI8605"))
    )
    (comp (ref "U11")
      (value "SI8600XSI8605")
      (footprint "eagle-import:SOIC16N")
      (libsource (lib "eagle-import") (part "SI8600XSI8605"))
    )
    (comp (ref "U12")
      (value "ATMEGA328P-A")
      (footprint "eagle-import:TQFP32A")
      (libsource (lib "eagle-import") (part "ATMEGA48P/88P/168P/328P-A"))
    )
    (comp (ref "U13")
      (value "MCP3424-E/SL")
      (footprint "eagle-import:SOIC127P600X175-14N")
      (libsource (lib "eagle-import") (part "MCP3424-E/SL"))
    )
    (comp (ref "U14")
      (value "LM334Z")
      (footprint "eagle-import:TO92")
      (libsource (lib "eagle-import") (part "LM34Z3"))
    )
    (comp (ref "X1")
      (value "2-way")
      (footprint "eagle-import:W237-132")
      (libsource (lib "eagle-import") (part "W237-02P"))
    )
    (comp (ref "X2")
      (value "2-way")
      (footprint "eagle-import:W237-132")
      (libsource (lib "eagle-import") (part "W237-02P"))
    )
    (comp (ref "X3")
      (value "2-way")
      (footprint "eagle-import:W237-132")
      (libsource (lib "eagle-import") (part "W237-02P"))
    )
    (comp (ref "X4")
      (value "2-way")
      (footprint "eagle-import:W237-132")
      (libsource (lib "eagle-import") (part "W237-02P"))
    )
    (comp (ref "X5")
      (value "2-way")
      (footprint "eagle-import:W237-132")
      (libsource (lib "eagle-import") (part "W237-02P"))
    )
    (comp (ref "X6")
      (value "4-way SIL Pol")
      (footprint "eagle-import:22-23-2041")
      (fields (field (name "MF") "MOLEX") (field (name "MPN") "22-23-2041"))
      (libsource (lib "eagle-import") (part "22-23-2041"))
    )
    (comp (ref "X7")
      (value "6-way SIL Pol")
      (footprint "eagle-import:22-23-2061")
      (fields (field (name "MF") "MOLEX") (field (name "MPN") "22-23-2061"))
      (libsource (lib "eagle-import") (part "22-23-2061"))
    )
    (comp (ref "X8")
      (value "6-way SIL Pol")
      (footprint "eagle-import:22-23-2061")
      (fields (field (name "MF") "MOLEX") (field (name "MPN") "22-23-2061"))
      (libsource (lib "eagle-import") (part "22-23-2061"))
    )
    (comp (ref "XTAL1")
      (value "16MhZ")
      (footprint "eagle-import:HC49_S@1")
      (libsource (lib "eagle-import") (part "CRYTALHC49S"))
    )
  )
  (nets
    (net (code "1") (name "+5V") (class "Default")
      (node (ref "C49") (pin "1") (pinfunction "1_1") (pintype "passive"))
      (node (ref "C50") (pin "+") (pinfunction "+_+") (pintype "passive"))
      (node (ref "C51") (pin "+") (pinfunction "+_+") (pintype "passive"))
      (node (ref "C52") (pin "+") (pinfunction "+_+") (pintype "passive"))
      (node (ref "C54") (pin "2") (pinfunction "2_2") (pintype "passive"))
      (node (ref "C59") (pin "1") (pinfunction "1_1") (pintype "passive"))
      (node (ref "C61") (pin "1") (pinfunction "1_1") (pintype "passive"))
      (node (ref "C62") (pin "1") (pinfunction "1_1") (pintype "passive"))
      (node (ref "CON1") (pin "2") (pinfunction "2_2") (pintype "passive"))
      (node (ref "CON2") (pin "2") (pinfunction "2_2") (pintype "passive"))
      (node (ref "JP1") (pin "1") (pinfunction "1_1") (pintype "passive"))
      (node (ref "L5") (pin "2") (pinfunction "2_2") (pintype "passive"))
      (node (ref "R79") (pin "2") (pinfunction "2_2") (pintype "passive"))
      (node (ref "R80") (pin "1") (pinfunction "1_1") (pintype "passive"))
      (node (ref "R81") (pin "2") (pinfunction "2_2") (pintype "passive"))
      (node (ref "R82") (pin "2") (pinfunction "2_2") (pintype "passive"))
      (node (ref "R88") (pin "2") (pinfunction "2_2") (pintype "passive"))
      (node (ref "REG5") (pin "4") (pinfunction "FB_4") (pintype "input"))
      (node (ref "U10") (pin "1") (pinfunction "AVDD_1") (pintype "power_in"))
      (node (ref "U11") (pin "1") (pinfunction "AVDD_1") (pintype "power_in"))
      (node (ref "U12") (pin "18") (pinfunction "AVCC_18") (pintype "power_in"))
      (node (ref "U12") (pin "4") (pinfunction "VCC_4") (pintype "power_in"))
      (node (ref "U12") (pin "6") (pinfunction "VCC_6") (pintype "power_in"))
      (node (ref "U13") (pin "6") (pinfunction "VDD_6") (pintype "power_in"))
      (node (ref "X7") (pin "1") (pinfunction "S_1") (pintype "passive"))
    )
    (net (code "2") (name "+5Va") (class "Default")
      (node (ref "C30") (pin "+") (pinfunction "+_+") (pintype "passive"))
      (node (ref "C9") (pin "+") (pinfunction "+_+") (pintype "passive"))
      (node (ref "CS2") (pin "8") (pinfunction "VCC_8") (pintype "bidirectional"))
      (node (ref "R39") (pin "2") (pinfunction "2_2") (pintype "passive"))
      (node (ref "R75") (pin "2") (pinfunction "2_2") (pintype "passive"))
      (node (ref "R76") (pin "2") (pinfunction "2_2") (pintype "passive"))
      (node (ref "REG3") (pin "4") (pinfunction "OUT_4") (pintype "passive"))
      (node (ref "U10") (pin "16") (pinfunction "BVDD_16") (pintype "power_in"))
      (node (ref "U6") (pin "6") (pinfunction "VDD_6") (pintype "power_in"))
      (node (ref "U7") (pin "12") (pinfunction "IOVDD_12") (pintype "power_in"))
      (node (ref "U7") (pin "4") (pinfunction "VDD_4") (pintype "power_in"))
    )
    (net (code "3") (name "+5Vb") (class "Default")
      (node (ref "C10") (pin "+") (pinfunction "+_+") (pintype "passive"))
      (node (ref "C29") (pin "+") (pinfunction "+_+") (pintype "passive"))
      (node (ref "CS1") (pin "8") (pinfunction "VCC_8") (pintype "bidirectional"))
      (node (ref "R37") (pin "2") (pinfunction "2_2") (pintype "passive"))
      (node (ref "R77") (pin "2") (pinfunction "2_2") (pintype "passive"))
      (node (ref "R78") (pin "2") (pinfunction "2_2") (pintype "passive"))
      (node (ref "REG4") (pin "4") (pinfunction "OUT_4") (pintype "passive"))
      (node (ref "U11") (pin "16") (pinfunction "BVDD_16") (pintype "power_in"))
      (node (ref "U8") (pin "6") (pinfunction "VDD_6") (pintype "power_in"))
      (node (ref "U9") (pin "12") (pinfunction "IOVDD_12") (pintype "power_in"))
      (node (ref "U9") (pin "13") (pinfunction "A0_13") (pintype "input"))
      (node (ref "U9") (pin "4") (pinfunction "VDD_4") (pintype "power_in"))
    )
    (net (code "4") (name "+11.6V") (class "Default")
      (node (ref "C63") (pin "+") (pinfunction "+_+") (pintype "passive"))
      (node (ref "R86") (pin "2") (pinfunction "2_2") (pintype "passive"))
      (node (ref "REG7") (pin "4") (pinfunction "OUT_4") (pintype "passive"))
      (node (ref "X6") (pin "3") (pinfunction "S_3") (pintype "passive"))
    )
    (net (code "5") (name "+23.4V") (class "Default")
      (node (ref "C53") (pin "+") (pinfunction "+_+") (pintype "passive"))
      (node (ref "R83") (pin "2") (pinfunction "2_2") (pintype "passive"))
      (node (ref "R84") (pin "2") (pinfunction "2_2") (pintype "passive"))
      (node (ref "R87") (pin "1") (pinfunction "1_1") (pintype "passive"))
      (node (ref "REG6") (pin "4") (pinfunction "OUT_4") (pintype "passive"))
    )
    (net (code "6") (name "+30Vb") (class "Default")
      (node (ref "C20") (pin "+") (pinfunction "+_+") (pintype "passive"))
      (node (ref "C26") (pin "1") (pinfunction "1_1") (pintype "passive"))
      (node (ref "C36") (pin "1") (pinfunction "1_1") (pintype "passive"))
      (node (ref "C40") (pin "1") (pinfunction "1_1") (pintype "passive"))
      (node (ref "C46") (pin "1") (pinfunction "1_1") (pintype "passive"))
      (node (ref "D8") (pin "C") (pinfunction "C_C") (pintype "passive"))
      (node (ref "R30") (pin "1") (pinfunction "1_1") (pintype "passive"))
      (node (ref "R53") (pin "2") (pinfunction "2_2") (pintype "passive"))
      (node (ref "R66") (pin "2") (pinfunction "2_2") (pintype "passive"))
      (node (ref "REG4") (pin "3") (pinfunction "IN_3") (pintype "input"))
      (node (ref "U3") (pin "8") (pinfunction "VCC+_8") (pintype "power_in"))
      (node (ref "U5") (pin "8") (pinfunction "VCC+_8") (pintype "power_in"))
    )
    (net (code "7") (name "+30v") (class "Default")
      (node (ref "C19") (pin "+") (pinfunction "+_+") (pintype "passive"))
      (node (ref "C25") (pin "1") (pinfunction "1_1") (pintype "passive"))
      (node (ref "C35") (pin "1") (pinfunction "1_1") (pintype "passive"))
      (node (ref "C37") (pin "1") (pinfunction "1_1") (pintype "passive"))
      (node (ref "C44") (pin "1") (pinfunction "1_1") (pintype "passive"))
      (node (ref "D7") (pin "C") (pinfunction "C_C") (pintype "passive"))
      (node (ref "R26") (pin "1") (pinfunction "1_1") (pintype "passive"))
      (node (ref "R56") (pin "2") (pinfunction "2_2") (pintype "passive"))
      (node (ref "R65") (pin "2") (pinfunction "2_2") (pintype "passive"))
      (node (ref "REG3") (pin "3") (pinfunction "IN_3") (pintype "input"))
      (node (ref "U2") (pin "8") (pinfunction "VCC+_8") (pintype "power_in"))
      (node (ref "U4") (pin "8") (pinfunction "VCC+_8") (pintype "power_in"))
    )
    (net (code "8") (name "+Vb") (class "Default")
      (node (ref "BR1") (pin "+") (pinfunction "+_+") (pintype "passive"))
      (node (ref "C15") (pin "+") (pinfunction "+_+") (pintype "passive"))
      (node (ref "R30") (pin "2") (pinfunction "2_2") (pintype "passive"))
      (node (ref "REG2") (pin "1") (pinfunction "VIN_1") (pintype "input"))
    )
    (net (code "9") (name "/5VREF_1") (class "Default")
      (node (ref "C47") (pin "1") (pinfunction "1_1") (pintype "passive"))
      (node (ref "R65") (pin "1") (pinfunction "1_1") (pintype "passive"))
      (node (ref "REF3") (pin "1") (pinfunction "CATHODE_1") (pintype "output"))
      (node (ref "U7") (pin "3") (pinfunction "VREFH_3") (pintype "power_in"))
    )
    (net (code "10") (name "/5VREF_2") (class "Default")
      (node (ref "C48") (pin "1") (pinfunction "1_1") (pintype "passive"))
      (node (ref "R66") (pin "1") (pinfunction "1_1") (pintype "passive"))
      (node (ref "REF4") (pin "1") (pinfunction "CATHODE_1") (pintype "output"))
      (node (ref "U9") (pin "3") (pinfunction "VREFH_3") (pintype "power_in"))
    )
    (net (code "11") (name "/C.LIMIT.1") (class "Default")
      (node (ref "U10") (pin "5") (pinfunction "ADOUT_5") (pintype "bidirectional"))
      (node (ref "U12") (pin "11") (pinfunction "(PCINT23/AIN1)PD7_11") (pintype "bidirectional"))
    )
    (net (code "12") (name "/C.LIMIT.2") (class "Default")
      (node (ref "U11") (pin "5") (pinfunction "ADOUT_5") (pintype "bidirectional"))
      (node (ref "U12") (pin "10") (pinfunction "(PCINT22/OC0A/AIN0)PD6_10") (pintype "bidirectional"))
    )
    (net (code "13") (name "/CURRENT.POT.CH.1") (class "Default")
      (node (ref "U12") (pin "26") (pinfunction "(PCINT11/ADC3)PC3_26") (pintype "bidirectional"))
      (node (ref "X7") (pin "3") (pinfunction "S_3") (pintype "passive"))
    )
    (net (code "14") (name "/CURRENT.POT.CH.2") (class "Default")
      (node (ref "U12") (pin "25") (pinfunction "(PCINT10/ADC2)PC2_25") (pintype "bidirectional"))
      (node (ref "X7") (pin "2") (pinfunction "S_2") (pintype "passive"))
    )
    (net (code "15") (name "/FANPWM") (class "Default")
      (node (ref "R88") (pin "1") (pinfunction "1_1") (pintype "passive"))
      (node (ref "U12") (pin "1") (pinfunction "(PCINT19/OC2B/INT1)PD3_1") (pintype "bidirectional"))
      (node (ref "X6") (pin "1") (pinfunction "S_1") (pintype "passive"))
    )
    (net (code "16") (name "/IOUT.1") (class "Default")
      (node (ref "R71") (pin "2") (pinfunction "2_2") (pintype "passive"))
      (node (ref "R72") (pin "2") (pinfunction "2_2") (pintype "passive"))
      (node (ref "U6") (pin "13") (pinfunction "CH4+_13") (pintype "input"))
    )
    (net (code "17") (name "/IOUT.2") (class "Default")
      (node (ref "R73") (pin "2") (pinfunction "2_2") (pintype "passive"))
      (node (ref "R74") (pin "2") (pinfunction "2_2") (pintype "passive"))
      (node (ref "U8") (pin "13") (pinfunction "CH4+_13") (pintype "input"))
    )
    (net (code "18") (name "/LCD1_CS") (class "Default")
      (node (ref "CON2") (pin "3") (pinfunction "3_3") (pintype "passive"))
      (node (ref "U12") (pin "16") (pinfunction "(PCINT4/MISO)PB4_16") (pintype "bidirectional"))
    )
    (net (code "19") (name "/LCD1_SCLK") (class "Default")
      (node (ref "CON2") (pin "1") (pinfunction "1_1") (pintype "passive"))
      (node (ref "U12") (pin "17") (pinfunction "(PCINT5/SCK)PB5_17") (pintype "bidirectional"))
    )
    (net (code "20") (name "/LCD1_SID") (class "Default")
      (node (ref "CON2") (pin "5") (pinfunction "5_5") (pintype "passive"))
      (node (ref "U12") (pin "15") (pinfunction "(PCINT3/OC2A/MOSI)PB3_15") (pintype "bidirectional"))
    )
    (net (code "21") (name "/LCD2_CS") (class "Default")
      (node (ref "CON1") (pin "3") (pinfunction "3_3") (pintype "passive"))
      (node (ref "U12") (pin "13") (pinfunction "(PCINT1/OC1A)PB1_13") (pintype "bidirectional"))
    )
    (net (code "22") (name "/LCD2_SCLK") (class "Default")
      (node (ref "CON1") (pin "1") (pinfunction "1_1") (pintype "passive"))
      (node (ref "U12") (pin "14") (pinfunction "(PCINT2/SS/OC1B)PB2_14") (pintype "bidirectional"))
    )
    (net (code "23") (name "/LCD2_SID") (class "Default")
      (node (ref "CON1") (pin "5") (pinfunction "5_5") (pintype "passive"))
      (node (ref "U12") (pin "12") (pinfunction "(PCINT0/CLKO/ICP1)PB0_12") (pintype "bidirectional"))
    )
    (net (code "24") (name "/O.VOLCH.1") (class "Default")
      (node (ref "U13") (pin "11") (pinfunction "CH3+_11") (pintype "input"))
    )
    (net (code "25") (name "/O.VOLCH.2") (class "Default")
      (node (ref "U13") (pin "13") (pinfunction "CH4+_13") (pintype "input"))
    )
    (net (code "26") (name "/PREREGV.1") (class "Default")
      (node (ref "R17") (pin "2") (pinfunction "2_2") (pintype "passive"))
      (node (ref "R18") (pin "2") (pinfunction "2_2") (pintype "passive"))
      (node (ref "U6") (pin "3") (pinfunction "CH2+_3") (pintype "input"))
    )
    (net (code "27") (name "/PREREGV.2") (class "Default")
      (node (ref "R19") (pin "2") (pinfunction "2_2") (pintype "passive"))
      (node (ref "R20") (pin "2") (pinfunction "2_2") (pintype "passive"))
      (node (ref "U8") (pin "3") (pinfunction "CH2+_3") (pintype "input"))
    )
    (net (code "28") (name "/SCL") (class "Default")
      (node (ref "R81") (pin "1") (pinfunction "1_1") (pintype "passive"))
      (node (ref "U10") (pin "6") (pinfunction "ASCL_6") (pintype "bidirectional"))
      (node (ref "U11") (pin "6") (pinfunction "ASCL_6") (pintype "bidirectional"))
      (node (ref "U12") (pin "28") (pinfunction "(PCINT13/SCL/ADC5)PC5_28") (pintype "bidirectional"))
      (node (ref "U13") (pin "8") (pinfunction "SCL_8") (pintype "input"))
    )
    (net (code "29") (name "/SCL_1") (class "Default")
      (node (ref "R76") (pin "1") (pinfunction "1_1") (pintype "passive"))
      (node (ref "U10") (pin "11") (pinfunction "BSCL_11") (pintype "bidirectional"))
      (node (ref "U6") (pin "8") (pinfunction "SCL_8") (pintype "input"))
      (node (ref "U7") (pin "10") (pinfunction "SCL_10") (pintype "bidirectional"))
    )
    (net (code "30") (name "/SCL_2") (class "Default")
      (node (ref "R78") (pin "1") (pinfunction "1_1") (pintype "passive"))
      (node (ref "U11") (pin "11") (pinfunction "BSCL_11") (pintype "bidirectional"))
      (node (ref "U8") (pin "8") (pinfunction "SCL_8") (pintype "input"))
      (node (ref "U9") (pin "10") (pinfunction "SCL_10") (pintype "bidirectional"))
    )
    (net (code "31") (name "/SDA") (class "Default")
      (node (ref "R82") (pin "1") (pinfunction "1_1") (pintype "passive"))
      (node (ref "U10") (pin "3") (pinfunction "ASDA_3") (pintype "bidirectional"))
      (node (ref "U11") (pin "3") (pinfunction "ASDA_3") (pintype "bidirectional"))
      (node (ref "U12") (pin "27") (pinfunction "(PCINT12/SDA/ADC4)PC4_27") (pintype "bidirectional"))
      (node (ref "U13") (pin "7") (pinfunction "SDA_7") (pintype "bidirectional"))
    )
    (net (code "32") (name "/SDA_1") (class "Default")
      (node (ref "R75") (pin "1") (pinfunction "1_1") (pintype "passive"))
      (node (ref "U10") (pin "14") (pinfunction "BSDA_14") (pintype "bidirectional"))
      (node (ref "U6") (pin "7") (pinfunction "SDA_7") (pintype "bidirectional"))
      (node (ref "U7") (pin "11") (pinfunction "SDA_11") (pintype "bidirectional"))
    )
    (net (code "33") (name "/SDA_2") (class "Default")
      (node (ref "R77") (pin "1") (pinfunction "1_1") (pintype "passive"))
      (node (ref "U11") (pin "14") (pinfunction "BSDA_14") (pintype "bidirectional"))
      (node (ref "U8") (pin "7") (pinfunction "SDA_7") (pintype "bidirectional"))
      (node (ref "U9") (pin "11") (pinfunction "SDA_11") (pintype "bidirectional"))
    )
    (net (code "34") (name "/SW1") (class "Default")
      (node (ref "U12") (pin "2") (pinfunction "(PCINT20/XCK/T0)PD4_2") (pintype "bidirectional"))
      (node (ref "X7") (pin "5") (pinfunction "S_5") (pintype "passive"))
    )
    (net (code "35") (name "/SW2") (class "Default")
      (node (ref "U12") (pin "9") (pinfunction "(PCINT21/OC0B/T1)PD5_9") (pintype "bidirectional"))
      (node (ref "X7") (pin "4") (pinfunction "S_4") (pintype "passive"))
    )
    (net (code "36") (name "/VOUT.1") (class "Default")
      (node (ref "C4") (pin "2") (pinfunction "2_2") (pintype "passive"))
      (node (ref "R2") (pin "2") (pinfunction "2_2") (pintype "passive"))
      (node (ref "R4") (pin "2") (pinfunction "2_2") (pintype "passive"))
      (node (ref "U6") (pin "11") (pinfunction "CH3+_11") (pintype "input"))
    )
    (net (code "37") (name "/VOUT.2") (class "Default")
      (node (ref "C2") (pin "2") (pinfunction "2_2") (pintype "passive"))
      (node (ref "R1") (pin "2") (pinfunction "2_2") (pintype "passive"))
      (node (ref "R3") (pin "2") (pinfunction "2_2") (pintype "passive"))
      (node (ref "U8") (pin "11") (pinfunction "CH3+_11") (pintype "input"))
    )
    (net (code "38") (name "AGND") (class "Default")
      (node (ref "BR2") (pin "-") (pinfunction "-_-") (pintype "passive"))
      (node (ref "C11") (pin "-") (pinfunction "-_-") (pintype "passive"))
      (node (ref "C13") (pin "-") (pinfunction "-_-") (pintype "passive"))
      (node (ref "C16") (pin "-") (pinfunction "-_-") (pintype "passive"))
      (node (ref "C17") (pin "-") (pinfunction "-_-") (pintype "passive"))
      (node (ref "C19") (pin "-") (pinfunction "-_-") (pintype "passive"))
      (node (ref "C21") (pin "2") (pinfunction "2_2") (pintype "passive"))
      (node (ref "C25") (pin "2") (pinfunction "2_2") (pintype "passive"))
      (node (ref "C28") (pin "2") (pinfunction "2_2") (pintype "passive"))
      (node (ref "C3") (pin "2") (pinfunction "2_2") (pintype "passive"))
      (node (ref "C30") (pin "-") (pinfunction "-_-") (pintype "passive"))
      (node (ref "C33") (pin "1") (pinfunction "1_1") (pintype "passive"))
      (node (ref "C35") (pin "2") (pinfunction "2_2") (pintype "passive"))
      (node (ref "C37") (pin "2") (pinfunction "2_2") (pintype "passive"))
      (node (ref "C38") (pin "2") (pinfunction "2_2") (pintype "passive"))
      (node (ref "C4") (pin "1") (pinfunction "1_1") (pintype "passive"))
      (node (ref "C41") (pin "2") (pinfunction "2_2") (pintype "passive"))
      (node (ref "C44") (pin "2") (pinfunction "2_2") (pintype "passive"))
      (node (ref "C47") (pin "2") (pinfunction "2_2") (pintype "passive"))
      (node (ref "C5") (pin "-") (pinfunction "-_-") (pintype "passive"))
      (node (ref "C6") (pin "-") (pinfunction "-_-") (pintype "passive"))
      (node (ref "C9") (pin "-") (pinfunction "-_-") (pintype "passive"))
      (node (ref "CS2") (pin "5") (pinfunction "GND_5") (pintype "bidirectional"))
      (node (ref "D1") (pin "A") (pinfunction "A_A") (pintype "passive"))
      (node (ref "D7") (pin "A") (pinfunction "A_A") (pintype "passive"))
      (node (ref "D9") (pin "A") (pinfunction "A_A") (pintype "passive"))
      (node (ref "Q11") (pin "2") (pinfunction "E_2") (pintype "passive"))
      (node (ref "R17") (pin "1") (pinfunction "1_1") (pintype "passive"))
      (node (ref "R2") (pin "1") (pinfunction "1_1") (pintype "passive"))
      (node (ref "R38") (pin "1") (pinfunction "1_1") (pintype "passive"))
      (node (ref "R52") (pin "1") (pinfunction "1_1") (pintype "passive"))
      (node (ref "R58") (pin "2") (pinfunction "2_2") (pintype "passive"))
      (node (ref "R6") (pin "2") (pinfunction "2_2") (pintype "passive"))
      (node (ref "R71") (pin "1") (pinfunction "1_1") (pintype "passive"))
      (node (ref "R8") (pin "1") (pinfunction "1_1") (pintype "passive"))
      (node (ref "REF1") (pin "2") (pinfunction "A_2") (pintype "input"))
      (node (ref "REF3") (pin "2") (pinfunction "A_2") (pintype "input"))
      (node (ref "REG1") (pin "3") (pinfunction "GND_3") (pintype "input"))
      (node (ref "REG1") (pin "5") (pinfunction "~{ON/OFF}_5") (pintype "input"))
      (node (ref "U10") (pin "9") (pinfunction "BGND_9") (pintype "power_in"))
      (node (ref "U14") (pin "3") (pinfunction "V-_3") (pintype "passive"))
      (node (ref "U2") (pin "4") (pinfunction "VCC-_4") (pintype "power_in"))
      (node (ref "U4") (pin "4") (pinfunction "VCC-_4") (pintype "power_in"))
      (node (ref "U6") (pin "12") (pinfunction "CH3-_12") (pintype "input"))
      (node (ref "U6") (pin "14") (pinfunction "CH4-_14") (pintype "input"))
      (node (ref "U6") (pin "2") (pinfunction "CH1-_2") (pintype "input"))
      (node (ref "U6") (pin "4") (pinfunction "CH2-_4") (pintype "input"))
      (node (ref "U6") (pin "5") (pinfunction "VSS_5") (pintype "power_in"))
      (node (ref "U6") (pin "9") (pinfunction "ADR0_9") (pintype "input"))
      (node (ref "U7") (pin "13") (pinfunction "A0_13") (pintype "input"))
      (node (ref "U7") (pin "14") (pinfunction "A1_14") (pintype "input"))
      (node (ref "U7") (pin "15") (pinfunction "A2_15") (pintype "input"))
      (node (ref "U7") (pin "16") (pinfunction "A3_16") (pintype "input"))
      (node (ref "U7") (pin "5") (pinfunction "VREFL_5") (pintype "power_in"))
      (node (ref "U7") (pin "6") (pinfunction "GND_6") (pintype "power_in"))
      (node (ref "U7") (pin "9") (pinfunction "LDAC_9") (pintype "input"))
      (node (ref "X2") (pin "1") (pinfunction "KL_1") (pintype "passive"))
    )
    (net (code "39") (name "GND") (class "Default")
      (node (ref "BR3") (pin "-") (pinfunction "-_-") (pintype "passive"))
      (node (ref "C49") (pin "2") (pinfunction "2_2") (pintype "passive"))
      (node (ref "C50") (pin "-") (pinfunction "-_-") (pintype "passive"))
      (node (ref "C51") (pin "-") (pinfunction "-_-") (pintype "passive"))
      (node (ref "C52") (pin "-") (pinfunction "-_-") (pintype "passive"))
      (node (ref "C53") (pin "-") (pinfunction "-_-") (pintype "passive"))
      (node (ref "C54") (pin "1") (pinfunction "1_1") (pintype "passive"))
      (node (ref "C56") (pin "1") (pinfunction "1_1") (pintype "passive"))
      (node (ref "C57") (pin "2") (pinfunction "2_2") (pintype "passive"))
      (node (ref "C58") (pin "2") (pinfunction "2_2") (pintype "passive"))
      (node (ref "C59") (pin "2") (pinfunction "2_2") (pintype "passive"))
      (node (ref "C60") (pin "1") (pinfunction "1_1") (pintype "passive"))
      (node (ref "C61") (pin "2") (pinfunction "2_2") (pintype "passive"))
      (node (ref "C62") (pin "2") (pinfunction "2_2") (pintype "passive"))
      (node (ref "C63") (pin "-") (pinfunction "-_-") (pintype "passive"))
      (node (ref "C64") (pin "2") (pinfunction "2_2") (pintype "passive"))
      (node (ref "C65") (pin "2") (pinfunction "2_2") (pintype "passive"))
      (node (ref "C66") (pin "-") (pinfunction "-_-") (pintype "passive"))
      (node (ref "CON1") (pin "6") (pinfunction "6_6") (pintype "passive"))
      (node (ref "CON2") (pin "6") (pinfunction "6_6") (pintype "passive"))
      (node (ref "D11") (pin "A") (pinfunction "A_A") (pintype "passive"))
      (node (ref "FTDI") (pin "5") (pinfunction "CTS_5") (pintype "passive"))
      (node (ref "FTDI") (pin "6") (pinfunction "GND_6") (pintype "passive"))
      (node (ref "LD1") (pin "K") (pinfunction "C_K") (pintype "passive"))
      (node (ref "R85") (pin "1") (pinfunction "1_1") (pintype "passive"))
      (node (ref "R89") (pin "1") (pinfunction "1_1") (pintype "passive"))
      (node (ref "REF5") (pin "2") (pinfunction "A_2") (pintype "input"))
      (node (ref "REF6") (pin "2") (pinfunction "A_2") (pintype "input"))
      (node (ref "REG5") (pin "3") (pinfunction "GND_3") (pintype "input"))
      (node (ref "REG5") (pin "5") (pinfunction "~{ON/OFF}_5") (pintype "input"))
      (node (ref "S1") (pin "1") (pinfunction "1_1") (pintype "passive"))
      (node (ref "S1") (pin "2") (pinfunction "2_2") (pintype "passive"))
      (node (ref "U10") (pin "8") (pinfunction "AGND_8") (pintype "power_in"))
      (node (ref "U11") (pin "8") (pinfunction "AGND_8") (pintype "power_in"))
      (node (ref "U12") (pin "21") (pinfunction "GND_21") (pintype "power_in"))
      (node (ref "U12") (pin "3") (pinfunction "GND_3") (pintype "power_in"))
      (node (ref "U12") (pin "5") (pinfunction "GND_5") (pintype "power_in"))
      (node (ref "U13") (pin "10") (pinfunction "ADR1_10") (pintype "input"))
      (node (ref "U13") (pin "12") (pinfunction "CH3-_12") (pintype "input"))
      (node (ref "U13") (pin "14") (pinfunction "CH4-_14") (pintype "input"))
      (node (ref "U13") (pin "2") (pinfunction "CH1-_2") (pintype "input"))
      (node (ref "U13") (pin "4") (pinfunction "CH2-_4") (pintype "input"))
      (node (ref "U13") (pin "5") (pinfunction "VSS_5") (pintype "power_in"))
      (node (ref "U13") (pin "9") (pinfunction "ADR0_9") (pintype "input"))
      (node (ref "X6") (pin "4") (pinfunction "S_4") (pintype "passive"))
      (node (ref "X7") (pin "6") (pinfunction "S_6") (pintype "passive"))
      (node (ref "X8") (pin "3") (pinfunction "S_3") (pintype "passive"))
      (node (ref "X8") (pin "6") (pinfunction "S_6") (pintype "passive"))
    )
    (net (code "40") (name "GND1") (class "Default")
      (node (ref "BR1") (pin "-") (pinfunction "-_-") (pintype "passive"))
      (node (ref "C1") (pin "2") (pinfunction "2_2") (pintype "passive"))
      (node (ref "C10") (pin "-") (pinfunction "-_-") (pintype "passive"))
      (node (ref "C12") (pin "-") (pinfunction "-_-") (pintype "passive"))
      (node (ref "C14") (pin "-") (pinfunction "-_-") (pintype "passive"))
      (node (ref "C15") (pin "-") (pinfunction "-_-") (pintype "passive"))
      (node (ref "C18") (pin "-") (pinfunction "-_-") (pintype "passive"))
      (node (ref "C2") (pin "1") (pinfunction "1_1") (pintype "passive"))
      (node (ref "C20") (pin "-") (pinfunction "-_-") (pintype "passive"))
      (node (ref "C22") (pin "2") (pinfunction "2_2") (pintype "passive"))
      (node (ref "C26") (pin "2") (pinfunction "2_2") (pintype "passive"))
      (node (ref "C27") (pin "2") (pinfunction "2_2") (pintype "passive"))
      (node (ref "C29") (pin "-") (pinfunction "-_-") (pintype "passive"))
      (node (ref "C34") (pin "1") (pinfunction "1_1") (pintype "passive"))
      (node (ref "C36") (pin "2") (pinfunction "2_2") (pintype "passive"))
      (node (ref "C39") (pin "2") (pinfunction "2_2") (pintype "passive"))
      (node (ref "C40") (pin "2") (pinfunction "2_2") (pintype "passive"))
      (node (ref "C43") (pin "2") (pinfunction "2_2") (pintype "passive"))
      (node (ref "C46") (pin "2") (pinfunction "2_2") (pintype "passive"))
      (node (ref "C48") (pin "2") (pinfunction "2_2") (pintype "passive"))
      (node (ref "C7") (pin "-") (pinfunction "-_-") (pintype "passive"))
      (node (ref "C8") (pin "-") (pinfunction "-_-") (pintype "passive"))
      (node (ref "CS1") (pin "5") (pinfunction "GND_5") (pintype "bidirectional"))
      (node (ref "D10") (pin "A") (pinfunction "A_A") (pintype "passive"))
      (node (ref "D2") (pin "A") (pinfunction "A_A") (pintype "passive"))
      (node (ref "D8") (pin "A") (pinfunction "A_A") (pintype "passive"))
      (node (ref "Q12") (pin "2") (pinfunction "E_2") (pintype "passive"))
      (node (ref "R1") (pin "1") (pinfunction "1_1") (pintype "passive"))
      (node (ref "R19") (pin "1") (pinfunction "1_1") (pintype "passive"))
      (node (ref "R36") (pin "1") (pinfunction "1_1") (pintype "passive"))
      (node (ref "R5") (pin "2") (pinfunction "2_2") (pintype "passive"))
      (node (ref "R51") (pin "1") (pinfunction "1_1") (pintype "passive"))
      (node (ref "R60") (pin "2") (pinfunction "2_2") (pintype "passive"))
      (node (ref "R7") (pin "1") (pinfunction "1_1") (pintype "passive"))
      (node (ref "R73") (pin "1") (pinfunction "1_1") (pintype "passive"))
      (node (ref "REF2") (pin "2") (pinfunction "A_2") (pintype "input"))
      (node (ref "REF4") (pin "2") (pinfunction "A_2") (pintype "input"))
      (node (ref "REG2") (pin "3") (pinfunction "GND_3") (pintype "input"))
      (node (ref "REG2") (pin "5") (pinfunction "~{ON/OFF}_5") (pintype "input"))
      (node (ref "U1") (pin "3") (pinfunction "V-_3") (pintype "passive"))
      (node (ref "U11") (pin "9") (pinfunction "BGND_9") (pintype "power_in"))
      (node (ref "U3") (pin "4") (pinfunction "VCC-_4") (pintype "power_in"))
      (node (ref "U5") (pin "4") (pinfunction "VCC-_4") (pintype "power_in"))
      (node (ref "U8") (pin "10") (pinfunction "ADR1_10") (pintype "input"))
      (node (ref "U8") (pin "12") (pinfunction "CH3-_12") (pintype "input"))
      (node (ref "U8") (pin "14") (pinfunction "CH4-_14") (pintype "input"))
      (node (ref "U8") (pin "2") (pinfunction "CH1-_2") (pintype "input"))
      (node (ref "U8") (pin "4") (pinfunction "CH2-_4") (pintype "input"))
      (node (ref "U8") (pin "5") (pinfunction "VSS_5") (pintype "power_in"))
      (node (ref "U9") (pin "14") (pinfunction "A1_14") (pintype "input"))
      (node (ref "U9") (pin "15") (pinfunction "A2_15") (pintype "input"))
      (node (ref "U9") (pin "16") (pinfunction "A3_16") (pintype "input"))
      (node (ref "U9") (pin "5") (pinfunction "VREFL_5") (pintype "power_in"))
      (node (ref "U9") (pin "6") (pinfunction "GND_6") (pintype "power_in"))
      (node (ref "U9") (pin "9") (pinfunction "LDAC_9") (pintype "input"))
      (node (ref "X1") (pin "1") (pinfunction "KL_1") (pintype "passive"))
    )
    (net (code "41") (name "Net-(C5-Pad+)") (class "Default")
      (node (ref "C5") (pin "+") (pinfunction "+_+") (pintype "passive"))
      (node (ref "C6") (pin "+") (pinfunction "+_+") (pintype "passive"))
      (node (ref "L1") (pin "1") (pinfunction "1_1") (pintype "passive"))
      (node (ref "L3") (pin "2") (pinfunction "2_2") (pintype "passive"))
      (node (ref "R10") (pin "1") (pinfunction "1_1") (pintype "passive"))
    )
    (net (code "42") (name "Net-(C7-Pad+)") (class "Default")
      (node (ref "C7") (pin "+") (pinfunction "+_+") (pintype "passive"))
      (node (ref "C8") (pin "+") (pinfunction "+_+") (pintype "passive"))
      (node (ref "L2") (pin "1") (pinfunction "1_1") (pintype "passive"))
      (node (ref "L4") (pin "2") (pinfunction "2_2") (pintype "passive"))
      (node (ref "R9") (pin "1") (pinfunction "1_1") (pintype "passive"))
    )
    (net (code "43") (name "Net-(CS1-FILT)") (class "Default")
      (node (ref "C1") (pin "1") (pinfunction "1_1") (pintype "passive"))
      (node (ref "CS1") (pin "6") (pinfunction "FILT_6") (pintype "bidirectional"))
    )
    (net (code "44") (name "Net-(CS1-VOUT)") (class "Default")
      (node (ref "C39") (pin "1") (pinfunction "1_1") (pintype "passive"))
      (node (ref "CS1") (pin "7") (pinfunction "VOUT_7") (pintype "bidirectional"))
      (node (ref "R62") (pin "2") (pinfunction "2_2") (pintype "passive"))
    )
    (net (code "45") (name "Net-(CS2-FILT)") (class "Default")
      (node (ref "C3") (pin "1") (pinfunction "1_1") (pintype "passive"))
      (node (ref "CS2") (pin "6") (pinfunction "FILT_6") (pintype "bidirectional"))
    )
    (net (code "46") (name "Net-(CS2-VOUT)") (class "Default")
      (node (ref "C38") (pin "1") (pinfunction "1_1") (pintype "passive"))
      (node (ref "CS2") (pin "7") (pinfunction "VOUT_7") (pintype "bidirectional"))
      (node (ref "R61") (pin "2") (pinfunction "2_2") (pintype "passive"))
    )
    (net (code "47") (name "Net-(D3-+)") (class "Default")
      (node (ref "D3") (pin "A") (pinfunction "+_A") (pintype "passive"))
      (node (ref "Q1") (pin "E") (pinfunction "E_E") (pintype "passive"))
    )
    (net (code "48") (name "Net-(D3--)") (class "Default")
      (node (ref "C13") (pin "+") (pinfunction "+_+") (pintype "passive"))
      (node (ref "C17") (pin "+") (pinfunction "+_+") (pintype "passive"))
      (node (ref "D3") (pin "C") (pinfunction "-_C") (pintype "passive"))
      (node (ref "D5") (pin "C") (pinfunction "-_C") (pintype "passive"))
      (node (ref "L1") (pin "2") (pinfunction "2_2") (pintype "passive"))
      (node (ref "Q3") (pin "C") (pinfunction "C_C") (pintype "passive"))
      (node (ref "Q4") (pin "C") (pinfunction "C_C") (pintype "passive"))
      (node (ref "Q5") (pin "C") (pinfunction "C_C") (pintype "passive"))
      (node (ref "Q6") (pin "2") (pinfunction "C_2") (pintype "passive"))
      (node (ref "R18") (pin "1") (pinfunction "1_1") (pintype "passive"))
    )
    (net (code "49") (name "Net-(D4-+)") (class "Default")
      (node (ref "D4") (pin "A") (pinfunction "+_A") (pintype "passive"))
      (node (ref "Q2") (pin "E") (pinfunction "E_E") (pintype "passive"))
    )
    (net (code "50") (name "Net-(D4--)") (class "Default")
      (node (ref "C14") (pin "+") (pinfunction "+_+") (pintype "passive"))
      (node (ref "C18") (pin "+") (pinfunction "+_+") (pintype "passive"))
      (node (ref "D4") (pin "C") (pinfunction "-_C") (pintype "passive"))
      (node (ref "D6") (pin "C") (pinfunction "-_C") (pintype "passive"))
      (node (ref "L2") (pin "2") (pinfunction "2_2") (pintype "passive"))
      (node (ref "Q10") (pin "2") (pinfunction "C_2") (pintype "passive"))
      (node (ref "Q7") (pin "C") (pinfunction "C_C") (pintype "passive"))
      (node (ref "Q8") (pin "C") (pinfunction "C_C") (pintype "passive"))
      (node (ref "Q9") (pin "C") (pinfunction "C_C") (pintype "passive"))
      (node (ref "R20") (pin "1") (pinfunction "1_1") (pintype "passive"))
    )
    (net (code "51") (name "Net-(D5-+)") (class "Default")
      (node (ref "D5") (pin "A") (pinfunction "+_A") (pintype "passive"))
      (node (ref "Q1") (pin "B") (pinfunction "B_B") (pintype "passive"))
      (node (ref "R21") (pin "2") (pinfunction "2_2") (pintype "passive"))
    )
    (net (code "52") (name "Net-(D6-+)") (class "Default")
      (node (ref "D6") (pin "A") (pinfunction "+_A") (pintype "passive"))
      (node (ref "Q2") (pin "B") (pinfunction "B_B") (pintype "passive"))
      (node (ref "R22") (pin "2") (pinfunction "2_2") (pintype "passive"))
    )
    (net (code "53") (name "Net-(FTDI-DTR)") (class "Default")
      (node (ref "C55") (pin "1") (pinfunction "1_1") (pintype "passive"))
      (node (ref "FTDI") (pin "1") (pinfunction "DTR_1") (pintype "passive"))
    )
    (net (code "54") (name "Net-(FTDI-RXI)") (class "Default")
      (node (ref "FTDI") (pin "2") (pinfunction "RXI_2") (pintype "passive"))
      (node (ref "U12") (pin "31") (pinfunction "(PCINT17/TXD)PD1_31") (pintype "bidirectional"))
    )
    (net (code "55") (name "Net-(FTDI-TXO)") (class "Default")
      (node (ref "FTDI") (pin "3") (pinfunction "TXO_3") (pintype "passive"))
      (node (ref "U12") (pin "30") (pinfunction "(PCINT16/RXD)PD0_30") (pintype "bidirectional"))
    )
    (net (code "56") (name "Net-(FTDI-VCC)") (class "Default")
      (node (ref "FTDI") (pin "4") (pinfunction "VCC_4") (pintype "passive"))
      (node (ref "JP1") (pin "2") (pinfunction "2_2") (pintype "passive"))
    )
    (net (code "57") (name "Net-(LD1-PadA)") (class "Default")
      (node (ref "LD1") (pin "A") (pinfunction "A_A") (pintype "passive"))
      (node (ref "R80") (pin "2") (pinfunction "2_2") (pintype "passive"))
    )
    (net (code "58") (name "Net-(Q3-PadB)") (class "Default")
      (node (ref "Q3") (pin "B") (pinfunction "B_B") (pintype "passive"))
      (node (ref "R23") (pin "1") (pinfunction "1_1") (pintype "passive"))
    )
    (net (code "59") (name "Net-(Q3-PadE)") (class "Default")
      (node (ref "Q3") (pin "E") (pinfunction "E_E") (pintype "passive"))
      (node (ref "R11") (pin "1") (pinfunction "1_1") (pintype "passive"))
    )
    (net (code "60") (name "Net-(Q4-PadB)") (class "Default")
      (node (ref "Q4") (pin "B") (pinfunction "B_B") (pintype "passive"))
      (node (ref "R24") (pin "1") (pinfunction "1_1") (pintype "passive"))
    )
    (net (code "61") (name "Net-(Q4-PadE)") (class "Default")
      (node (ref "Q4") (pin "E") (pinfunction "E_E") (pintype "passive"))
      (node (ref "R12") (pin "1") (pinfunction "1_1") (pintype "passive"))
    )
    (net (code "62") (name "Net-(Q5-PadB)") (class "Default")
      (node (ref "Q5") (pin "B") (pinfunction "B_B") (pintype "passive"))
      (node (ref "R25") (pin "1") (pinfunction "1_1") (pintype "passive"))
    )
    (net (code "63") (name "Net-(Q5-PadE)") (class "Default")
      (node (ref "Q5") (pin "E") (pinfunction "E_E") (pintype "passive"))
      (node (ref "R13") (pin "1") (pinfunction "1_1") (pintype "passive"))
    )
    (net (code "64") (name "Net-(Q6-B)") (class "Default")
      (node (ref "Q6") (pin "1") (pinfunction "B_1") (pintype "passive"))
      (node (ref "R32") (pin "1") (pinfunction "1_1") (pintype "passive"))
    )
    (net (code "65") (name "Net-(Q6-E)") (class "Default")
      (node (ref "Q6") (pin "3") (pinfunction "E_3") (pintype "passive"))
      (node (ref "R23") (pin "2") (pinfunction "2_2") (pintype "passive"))
      (node (ref "R24") (pin "2") (pinfunction "2_2") (pintype "passive"))
      (node (ref "R25") (pin "2") (pinfunction "2_2") (pintype "passive"))
    )
    (net (code "66") (name "Net-(Q7-PadB)") (class "Default")
      (node (ref "Q7") (pin "B") (pinfunction "B_B") (pintype "passive"))
      (node (ref "R27") (pin "1") (pinfunction "1_1") (pintype "passive"))
    )
    (net (code "67") (name "Net-(Q7-PadE)") (class "Default")
      (node (ref "Q7") (pin "E") (pinfunction "E_E") (pintype "passive"))
      (node (ref "R14") (pin "1") (pinfunction "1_1") (pintype "passive"))
    )
    (net (code "68") (name "Net-(Q8-PadB)") (class "Default")
      (node (ref "Q8") (pin "B") (pinfunction "B_B") (pintype "passive"))
      (node (ref "R28") (pin "1") (pinfunction "1_1") (pintype "passive"))
    )
    (net (code "69") (name "Net-(Q8-PadE)") (class "Default")
      (node (ref "Q8") (pin "E") (pinfunction "E_E") (pintype "passive"))
      (node (ref "R15") (pin "1") (pinfunction "1_1") (pintype "passive"))
    )
    (net (code "70") (name "Net-(Q9-PadB)") (class "Default")
      (node (ref "Q9") (pin "B") (pinfunction "B_B") (pintype "passive"))
      (node (ref "R29") (pin "1") (pinfunction "1_1") (pintype "passive"))
    )
    (net (code "71") (name "Net-(Q9-PadE)") (class "Default")
      (node (ref "Q9") (pin "E") (pinfunction "E_E") (pintype "passive"))
      (node (ref "R16") (pin "1") (pinfunction "1_1") (pintype "passive"))
    )
    (net (code "72") (name "Net-(Q10-B)") (class "Default")
      (node (ref "Q10") (pin "1") (pinfunction "B_1") (pintype "passive"))
      (node (ref "R33") (pin "1") (pinfunction "1_1") (pintype "passive"))
    )
    (net (code "73") (name "Net-(Q10-E)") (class "Default")
      (node (ref "Q10") (pin "3") (pinfunction "E_3") (pintype "passive"))
      (node (ref "R27") (pin "2") (pinfunction "2_2") (pintype "passive"))
      (node (ref "R28") (pin "2") (pinfunction "2_2") (pintype "passive"))
      (node (ref "R29") (pin "2") (pinfunction "2_2") (pintype "passive"))
    )
    (net (code "74") (name "Net-(Q11-B)") (class "Default")
      (node (ref "Q11") (pin "1") (pinfunction "B_1") (pintype "passive"))
      (node (ref "R31") (pin "2") (pinfunction "2_2") (pintype "passive"))
    )
    (net (code "75") (name "Net-(Q11-C)") (class "Default")
      (node (ref "Q11") (pin "3") (pinfunction "C_3") (pintype "passive"))
      (node (ref "R32") (pin "2") (pinfunction "2_2") (pintype "passive"))
      (node (ref "R55") (pin "2") (pinfunction "2_2") (pintype "passive"))
    )
    (net (code "76") (name "Net-(Q12-B)") (class "Default")
      (node (ref "Q12") (pin "1") (pinfunction "B_1") (pintype "passive"))
      (node (ref "R34") (pin "2") (pinfunction "2_2") (pintype "passive"))
    )
    (net (code "77") (name "Net-(Q12-C)") (class "Default")
      (node (ref "Q12") (pin "3") (pinfunction "C_3") (pintype "passive"))
      (node (ref "R33") (pin "2") (pinfunction "2_2") (pintype "passive"))
      (node (ref "R54") (pin "2") (pinfunction "2_2") (pintype "passive"))
    )
    (net (code "78") (name "Net-(R43-A)") (class "Default")
      (node (ref "C12") (pin "+") (pinfunction "+_+") (pintype "passive"))
      (node (ref "CS1") (pin "1") (pinfunction "IP+_1") (pintype "bidirectional"))
      (node (ref "CS1") (pin "2") (pinfunction "IP+_2") (pintype "bidirectional"))
      (node (ref "R14") (pin "2") (pinfunction "2_2") (pintype "passive"))
      (node (ref "R15") (pin "2") (pinfunction "2_2") (pintype "passive"))
      (node (ref "R16") (pin "2") (pinfunction "2_2") (pintype "passive"))
      (node (ref "R22") (pin "1") (pinfunction "1_1") (pintype "passive"))
      (node (ref "R43") (pin "1") (pinfunction "A_1") (pintype "passive"))
      (node (ref "U1") (pin "1") (pinfunction "V+_1") (pintype "passive"))
    )
    (net (code "79") (name "Net-(R43-E)") (class "Default")
      (node (ref "R42") (pin "2") (pinfunction "2_2") (pintype "passive"))
      (node (ref "R43") (pin "2") (pinfunction "S_2") (pintype "passive"))
      (node (ref "R43") (pin "3") (pinfunction "E_3") (pintype "passive"))
    )
    (net (code "80") (name "Net-(R44-A)") (class "Default")
      (node (ref "C11") (pin "+") (pinfunction "+_+") (pintype "passive"))
      (node (ref "CS2") (pin "1") (pinfunction "IP+_1") (pintype "bidirectional"))
      (node (ref "CS2") (pin "2") (pinfunction "IP+_2") (pintype "bidirectional"))
      (node (ref "R11") (pin "2") (pinfunction "2_2") (pintype "passive"))
      (node (ref "R12") (pin "2") (pinfunction "2_2") (pintype "passive"))
      (node (ref "R13") (pin "2") (pinfunction "2_2") (pintype "passive"))
      (node (ref "R21") (pin "1") (pinfunction "1_1") (pintype "passive"))
      (node (ref "R44") (pin "1") (pinfunction "A_1") (pintype "passive"))
      (node (ref "U14") (pin "1") (pinfunction "V+_1") (pintype "passive"))
    )
    (net (code "81") (name "Net-(R44-E)") (class "Default")
      (node (ref "R40") (pin "2") (pinfunction "2_2") (pintype "passive"))
      (node (ref "R44") (pin "2") (pinfunction "S_2") (pintype "passive"))
      (node (ref "R44") (pin "3") (pinfunction "E_3") (pintype "passive"))
    )
    (net (code "82") (name "Net-(R47-A)") (class "Default")
      (node (ref "R47") (pin "1") (pinfunction "A_1") (pintype "passive"))
      (node (ref "R58") (pin "1") (pinfunction "1_1") (pintype "passive"))
    )
    (net (code "83") (name "Net-(R47-E)") (class "Default")
      (node (ref "R35") (pin "2") (pinfunction "2_2") (pintype "passive"))
      (node (ref "R47") (pin "3") (pinfunction "E_3") (pintype "passive"))
    )
    (net (code "84") (name "Net-(R47-S)") (class "Default")
      (node (ref "R47") (pin "2") (pinfunction "S_2") (pintype "passive"))
      (node (ref "R49") (pin "2") (pinfunction "2_2") (pintype "passive"))
    )
    (net (code "85") (name "Net-(R48-A)") (class "Default")
      (node (ref "R48") (pin "1") (pinfunction "A_1") (pintype "passive"))
      (node (ref "R60") (pin "1") (pinfunction "1_1") (pintype "passive"))
    )
    (net (code "86") (name "Net-(R48-E)") (class "Default")
      (node (ref "R41") (pin "2") (pinfunction "2_2") (pintype "passive"))
      (node (ref "R48") (pin "3") (pinfunction "E_3") (pintype "passive"))
    )
    (net (code "87") (name "Net-(R48-S)") (class "Default")
      (node (ref "R48") (pin "2") (pinfunction "S_2") (pintype "passive"))
      (node (ref "R50") (pin "2") (pinfunction "2_2") (pintype "passive"))
    )
    (net (code "88") (name "Net-(REF1-CATHODE)") (class "Default")
      (node (ref "C21") (pin "1") (pinfunction "1_1") (pintype "passive"))
      (node (ref "R35") (pin "1") (pinfunction "1_1") (pintype "passive"))
      (node (ref "R56") (pin "1") (pinfunction "1_1") (pintype "passive"))
      (node (ref "REF1") (pin "1") (pinfunction "CATHODE_1") (pintype "output"))
    )
    (net (code "89") (name "Net-(REF2-CATHODE)") (class "Default")
      (node (ref "C22") (pin "1") (pinfunction "1_1") (pintype "passive"))
      (node (ref "R41") (pin "1") (pinfunction "1_1") (pintype "passive"))
      (node (ref "R53") (pin "1") (pinfunction "1_1") (pintype "passive"))
      (node (ref "REF2") (pin "1") (pinfunction "CATHODE_1") (pintype "output"))
    )
    (net (code "90") (name "Net-(REF5-CATHODE)") (class "Default")
      (node (ref "C57") (pin "1") (pinfunction "1_1") (pintype "passive"))
      (node (ref "R84") (pin "1") (pinfunction "1_1") (pintype "passive"))
      (node (ref "REF5") (pin "1") (pinfunction "CATHODE_1") (pintype "output"))
      (node (ref "U12") (pin "20") (pinfunction "AREF_20") (pintype "bidirectional"))
      (node (ref "X8") (pin "4") (pinfunction "S_4") (pintype "passive"))
    )
    (net (code "91") (name "Net-(REF6-CATHODE)") (class "Default")
      (node (ref "C58") (pin "1") (pinfunction "1_1") (pintype "passive"))
      (node (ref "R87") (pin "2") (pinfunction "2_2") (pintype "passive"))
      (node (ref "REF6") (pin "1") (pinfunction "CATHODE_1") (pintype "output"))
      (node (ref "X8") (pin "1") (pinfunction "S_1") (pintype "passive"))
    )
    (net (code "92") (name "Net-(REG1-FB)") (class "Default")
      (node (ref "Q1") (pin "C") (pinfunction "C_C") (pintype "passive"))
      (node (ref "R10") (pin "2") (pinfunction "2_2") (pintype "passive"))
      (node (ref "R6") (pin "1") (pinfunction "1_1") (pintype "passive"))
      (node (ref "REG1") (pin "4") (pinfunction "FB_4") (pintype "input"))
    )
    (net (code "93") (name "Net-(REG1-OUT)") (class "Default")
      (node (ref "D1") (pin "C") (pinfunction "C_C") (pintype "passive"))
      (node (ref "L3") (pin "1") (pinfunction "1_1") (pintype "passive"))
      (node (ref "REG1") (pin "2") (pinfunction "OUT_2") (pintype "output"))
    )
    (net (code "94") (name "Net-(REG2-FB)") (class "Default")
      (node (ref "Q2") (pin "C") (pinfunction "C_C") (pintype "passive"))
      (node (ref "R5") (pin "1") (pinfunction "1_1") (pintype "passive"))
      (node (ref "R9") (pin "2") (pinfunction "2_2") (pintype "passive"))
      (node (ref "REG2") (pin "4") (pinfunction "FB_4") (pintype "input"))
    )
    (net (code "95") (name "Net-(REG2-OUT)") (class "Default")
      (node (ref "D2") (pin "C") (pinfunction "C_C") (pintype "passive"))
      (node (ref "L4") (pin "1") (pinfunction "1_1") (pintype "passive"))
      (node (ref "REG2") (pin "2") (pinfunction "OUT_2") (pintype "output"))
    )
    (net (code "96") (name "Net-(REG3-ADJ)") (class "Default")
      (node (ref "R38") (pin "2") (pinfunction "2_2") (pintype "passive"))
      (node (ref "R39") (pin "1") (pinfunction "1_1") (pintype "passive"))
      (node (ref "REG3") (pin "1") (pinfunction "ADJ_1") (pintype "input"))
    )
    (net (code "97") (name "Net-(REG4-ADJ)") (class "Default")
      (node (ref "R36") (pin "2") (pinfunction "2_2") (pintype "passive"))
      (node (ref "R37") (pin "1") (pinfunction "1_1") (pintype "passive"))
      (node (ref "REG4") (pin "1") (pinfunction "ADJ_1") (pintype "input"))
    )
    (net (code "98") (name "Net-(REG5-OUT)") (class "Default")
      (node (ref "D11") (pin "C") (pinfunction "C_C") (pintype "passive"))
      (node (ref "L5") (pin "1") (pinfunction "1_1") (pintype "passive"))
      (node (ref "REG5") (pin "2") (pinfunction "OUT_2") (pintype "output"))
    )
    (net (code "99") (name "Net-(REG6-ADJ)") (class "Default")
      (node (ref "R83") (pin "1") (pinfunction "1_1") (pintype "passive"))
      (node (ref "R85") (pin "2") (pinfunction "2_2") (pintype "passive"))
      (node (ref "REG6") (pin "1") (pinfunction "ADJ_1") (pintype "input"))
    )
    (net (code "100") (name "Net-(REG7-ADJ)") (class "Default")
      (node (ref "R86") (pin "1") (pinfunction "1_1") (pintype "passive"))
      (node (ref "R89") (pin "2") (pinfunction "2_2") (pintype "passive"))
      (node (ref "REG7") (pin "1") (pinfunction "ADJ_1") (pintype "input"))
    )
    (net (code "101") (name "Net-(U1-R)") (class "Default")
      (node (ref "R7") (pin "2") (pinfunction "2_2") (pintype "passive"))
      (node (ref "U1") (pin "2") (pinfunction "R_2") (pintype "passive"))
    )
    (net (code "102") (name "Net-(U2A-+IN)") (class "Default")
      (node (ref "C41") (pin "1") (pinfunction "1_1") (pintype "passive"))
      (node (ref "R61") (pin "1") (pinfunction "1_1") (pintype "passive"))
      (node (ref "U2") (pin "3") (pinfunction "+IN_3") (pintype "input"))
    )
    (net (code "103") (name "Net-(U2A--IN)") (class "Default")
      (node (ref "C42") (pin "2") (pinfunction "2_2") (pintype "passive"))
      (node (ref "R49") (pin "1") (pinfunction "1_1") (pintype "passive"))
      (node (ref "R57") (pin "2") (pinfunction "2_2") (pintype "passive"))
      (node (ref "U2") (pin "2") (pinfunction "-IN_2") (pintype "input"))
    )
    (net (code "104") (name "Net-(U2A-OUT)") (class "Default")
      (node (ref "C42") (pin "1") (pinfunction "1_1") (pintype "passive"))
      (node (ref "R45") (pin "2") (pinfunction "2_2") (pintype "passive"))
      (node (ref "R57") (pin "1") (pinfunction "1_1") (pintype "passive"))
      (node (ref "R72") (pin "1") (pinfunction "1_1") (pintype "passive"))
      (node (ref "U2") (pin "1") (pinfunction "OUT_1") (pintype "output"))
    )
    (net (code "105") (name "Net-(U2B-+IN)") (class "Default")
      (node (ref "R45") (pin "1") (pinfunction "1_1") (pintype "passive"))
      (node (ref "U2") (pin "5") (pinfunction "+IN_5") (pintype "input"))
    )
    (net (code "106") (name "Net-(U2B--IN)") (class "Default")
      (node (ref "C23") (pin "2") (pinfunction "2_2") (pintype "passive"))
      (node (ref "R67") (pin "1") (pinfunction "1_1") (pintype "passive"))
      (node (ref "U2") (pin "6") (pinfunction "-IN_6") (pintype "input"))
    )
    (net (code "107") (name "Net-(U2B-OUT)") (class "Default")
      (node (ref "C23") (pin "1") (pinfunction "1_1") (pintype "passive"))
      (node (ref "R31") (pin "1") (pinfunction "1_1") (pintype "passive"))
      (node (ref "R68") (pin "2") (pinfunction "2_2") (pintype "passive"))
      (node (ref "U2") (pin "7") (pinfunction "OUT_7") (pintype "output"))
    )
    (net (code "108") (name "Net-(U3A-+IN)") (class "Default")
      (node (ref "C43") (pin "1") (pinfunction "1_1") (pintype "passive"))
      (node (ref "R62") (pin "1") (pinfunction "1_1") (pintype "passive"))
      (node (ref "U3") (pin "3") (pinfunction "+IN_3") (pintype "input"))
    )
    (net (code "109") (name "Net-(U3A--IN)") (class "Default")
      (node (ref "C45") (pin "2") (pinfunction "2_2") (pintype "passive"))
      (node (ref "R50") (pin "1") (pinfunction "1_1") (pintype "passive"))
      (node (ref "R59") (pin "2") (pinfunction "2_2") (pintype "passive"))
      (node (ref "U3") (pin "2") (pinfunction "-IN_2") (pintype "input"))
    )
    (net (code "110") (name "Net-(U3A-OUT)") (class "Default")
      (node (ref "C45") (pin "1") (pinfunction "1_1") (pintype "passive"))
      (node (ref "R46") (pin "2") (pinfunction "2_2") (pintype "passive"))
      (node (ref "R59") (pin "1") (pinfunction "1_1") (pintype "passive"))
      (node (ref "R74") (pin "1") (pinfunction "1_1") (pintype "passive"))
      (node (ref "U3") (pin "1") (pinfunction "OUT_1") (pintype "output"))
    )
    (net (code "111") (name "Net-(U3B-+IN)") (class "Default")
      (node (ref "R46") (pin "1") (pinfunction "1_1") (pintype "passive"))
      (node (ref "U3") (pin "5") (pinfunction "+IN_5") (pintype "input"))
    )
    (net (code "112") (name "Net-(U3B--IN)") (class "Default")
      (node (ref "C24") (pin "2") (pinfunction "2_2") (pintype "passive"))
      (node (ref "R69") (pin "1") (pinfunction "1_1") (pintype "passive"))
      (node (ref "U3") (pin "6") (pinfunction "-IN_6") (pintype "input"))
    )
    (net (code "113") (name "Net-(U3B-OUT)") (class "Default")
      (node (ref "C24") (pin "1") (pinfunction "1_1") (pintype "passive"))
      (node (ref "R34") (pin "1") (pinfunction "1_1") (pintype "passive"))
      (node (ref "R70") (pin "2") (pinfunction "2_2") (pintype "passive"))
      (node (ref "U3") (pin "7") (pinfunction "OUT_7") (pintype "output"))
    )
    (net (code "114") (name "Net-(U4A-+IN)") (class "Default")
      (node (ref "U4") (pin "2") (pinfunction "-IN_2") (pintype "input"))
      (node (ref "U4") (pin "3") (pinfunction "+IN_3") (pintype "input"))
    )
    (net (code "115") (name "Net-(U4B-+IN)") (class "Default")
      (node (ref "C33") (pin "2") (pinfunction "2_2") (pintype "passive"))
      (node (ref "R63") (pin "2") (pinfunction "2_2") (pintype "passive"))
      (node (ref "U4") (pin "5") (pinfunction "+IN_5") (pintype "input"))
    )
    (net (code "116") (name "Net-(U4B--IN)") (class "Default")
      (node (ref "C28") (pin "1") (pinfunction "1_1") (pintype "passive"))
      (node (ref "C31") (pin "1") (pinfunction "1_1") (pintype "passive"))
      (node (ref "R40") (pin "1") (pinfunction "1_1") (pintype "passive"))
      (node (ref "R52") (pin "2") (pinfunction "2_2") (pintype "passive"))
      (node (ref "U4") (pin "6") (pinfunction "-IN_6") (pintype "input"))
    )
    (net (code "117") (name "Net-(U4B-OUT)") (class "Default")
      (node (ref "C31") (pin "2") (pinfunction "2_2") (pintype "passive"))
      (node (ref "R55") (pin "1") (pinfunction "1_1") (pintype "passive"))
      (node (ref "U4") (pin "7") (pinfunction "OUT_7") (pintype "output"))
    )
    (net (code "118") (name "Net-(U5A-+IN)") (class "Default")
      (node (ref "U5") (pin "2") (pinfunction "-IN_2") (pintype "input"))
      (node (ref "U5") (pin "3") (pinfunction "+IN_3") (pintype "input"))
    )
    (net (code "119") (name "Net-(U5B-+IN)") (class "Default")
      (node (ref "C34") (pin "2") (pinfunction "2_2") (pintype "passive"))
      (node (ref "R64") (pin "2") (pinfunction "2_2") (pintype "passive"))
      (node (ref "U5") (pin "5") (pinfunction "+IN_5") (pintype "input"))
    )
    (net (code "120") (name "Net-(U5B--IN)") (class "Default")
      (node (ref "C27") (pin "1") (pinfunction "1_1") (pintype "passive"))
      (node (ref "C32") (pin "1") (pinfunction "1_1") (pintype "passive"))
      (node (ref "R42") (pin "1") (pinfunction "1_1") (pintype "passive"))
      (node (ref "R51") (pin "2") (pinfunction "2_2") (pintype "passive"))
      (node (ref "U5") (pin "6") (pinfunction "-IN_6") (pintype "input"))
    )
    (net (code "121") (name "Net-(U5B-OUT)") (class "Default")
      (node (ref "C32") (pin "2") (pinfunction "2_2") (pintype "passive"))
      (node (ref "R54") (pin "1") (pinfunction "1_1") (pintype "passive"))
      (node (ref "U5") (pin "7") (pinfunction "OUT_7") (pintype "output"))
    )
    (net (code "122") (name "Net-(U7-VOUTA)") (class "Default")
      (node (ref "R63") (pin "1") (pinfunction "1_1") (pintype "passive"))
      (node (ref "U7") (pin "1") (pinfunction "VOUTA_1") (pintype "output"))
    )
    (net (code "123") (name "Net-(U7-VOUTB)") (class "Default")
      (node (ref "R67") (pin "2") (pinfunction "2_2") (pintype "passive"))
      (node (ref "U7") (pin "2") (pinfunction "VOUTB_2") (pintype "output"))
    )
    (net (code "124") (name "Net-(U9-VOUTA)") (class "Default")
      (node (ref "R64") (pin "1") (pinfunction "1_1") (pintype "passive"))
      (node (ref "U9") (pin "1") (pinfunction "VOUTA_1") (pintype "output"))
    )
    (net (code "125") (name "Net-(U9-VOUTB)") (class "Default")
      (node (ref "R69") (pin "2") (pinfunction "2_2") (pintype "passive"))
      (node (ref "U9") (pin "2") (pinfunction "VOUTB_2") (pintype "output"))
    )
    (net (code "126") (name "Net-(U10-BDIN)") (class "Default")
      (node (ref "D9") (pin "C") (pinfunction "C_C") (pintype "passive"))
      (node (ref "R68") (pin "1") (pinfunction "1_1") (pintype "passive"))
      (node (ref "U10") (pin "12") (pinfunction "BDIN_12") (pintype "bidirectional"))
    )
    (net (code "127") (name "Net-(U11-BDIN)") (class "Default")
      (node (ref "D10") (pin "C") (pinfunction "C_C") (pintype "passive"))
      (node (ref "R70") (pin "1") (pinfunction "1_1") (pintype "passive"))
      (node (ref "U11") (pin "12") (pinfunction "BDIN_12") (pintype "bidirectional"))
    )
    (net (code "128") (name "Net-(U12-(PCINT18{slash}INT0)PD2)") (class "Default")
      (node (ref "U12") (pin "32") (pinfunction "(PCINT18/INT0)PD2_32") (pintype "bidirectional"))
      (node (ref "X6") (pin "2") (pinfunction "S_2") (pintype "passive"))
    )
    (net (code "129") (name "Net-(U12-PB6(TOSC1{slash}XTAL1{slash}PCINT6))") (class "Default")
      (node (ref "C56") (pin "2") (pinfunction "2_2") (pintype "passive"))
      (node (ref "U12") (pin "7") (pinfunction "PB6(TOSC1/XTAL1/PCINT6)_7") (pintype "bidirectional"))
      (node (ref "XTAL1") (pin "2") (pinfunction "2_2") (pintype "passive"))
    )
    (net (code "130") (name "Net-(U12-PB7(TOSC2{slash}XTAL2{slash}PCINT7))") (class "Default")
      (node (ref "C60") (pin "2") (pinfunction "2_2") (pintype "passive"))
      (node (ref "U12") (pin "8") (pinfunction "PB7(TOSC2/XTAL2/PCINT7)_8") (pintype "bidirectional"))
      (node (ref "XTAL1") (pin "1") (pinfunction "1_1") (pintype "passive"))
    )
    (net (code "131") (name "Net-(U12-PC6(~{RESET}))") (class "Default")
      (node (ref "C55") (pin "2") (pinfunction "2_2") (pintype "passive"))
      (node (ref "R79") (pin "1") (pinfunction "1_1") (pintype "passive"))
      (node (ref "S1") (pin "3") (pinfunction "3_3") (pintype "passive"))
      (node (ref "S1") (pin "4") (pinfunction "4_4") (pintype "passive"))
      (node (ref "U12") (pin "29") (pinfunction "PC6(~{RESET})_29") (pintype "input"))
    )
    (net (code "132") (name "Net-(U13-CH1+)") (class "Default")
      (node (ref "C64") (pin "1") (pinfunction "1_1") (pintype "passive"))
      (node (ref "U13") (pin "1") (pinfunction "CH1+_1") (pintype "input"))
      (node (ref "X8") (pin "2") (pinfunction "S_2") (pintype "passive"))
    )
    (net (code "133") (name "Net-(U13-CH2+)") (class "Default")
      (node (ref "C65") (pin "1") (pinfunction "1_1") (pintype "passive"))
      (node (ref "U13") (pin "3") (pinfunction "CH2+_3") (pintype "input"))
      (node (ref "X8") (pin "5") (pinfunction "S_5") (pintype "passive"))
    )
    (net (code "134") (name "Net-(U14-R)") (class "Default")
      (node (ref "R8") (pin "2") (pinfunction "2_2") (pintype "passive"))
      (node (ref "U14") (pin "2") (pinfunction "R_2") (pintype "passive"))
    )
    (net (code "135") (name "Net-(X1B-KL)") (class "Default")
      (node (ref "CS1") (pin "3") (pinfunction "IP-_3") (pintype "bidirectional"))
      (node (ref "CS1") (pin "4") (pinfunction "IP-_4") (pintype "bidirectional"))
      (node (ref "R3") (pin "1") (pinfunction "1_1") (pintype "passive"))
      (node (ref "X1") (pin "2") (pinfunction "KL_2") (pintype "passive"))
    )
    (net (code "136") (name "Net-(X2B-KL)") (class "Default")
      (node (ref "CS2") (pin "3") (pinfunction "IP-_3") (pintype "bidirectional"))
      (node (ref "CS2") (pin "4") (pinfunction "IP-_4") (pintype "bidirectional"))
      (node (ref "R4") (pin "1") (pinfunction "1_1") (pintype "passive"))
      (node (ref "X2") (pin "2") (pinfunction "KL_2") (pintype "passive"))
    )
    (net (code "137") (name "Net-(X3A-KL)") (class "Default")
      (node (ref "BR2") (pin "AC1") (pinfunction "AC1_AC1") (pintype "passive"))
      (node (ref "X3") (pin "1") (pinfunction "KL_1") (pintype "passive"))
    )
    (net (code "138") (name "Net-(X3B-KL)") (class "Default")
      (node (ref "BR2") (pin "AC2") (pinfunction "AC2_AC2") (pintype "passive"))
      (node (ref "X3") (pin "2") (pinfunction "KL_2") (pintype "passive"))
    )
    (net (code "139") (name "Net-(X4A-KL)") (class "Default")
      (node (ref "BR1") (pin "AC1") (pinfunction "AC1_AC1") (pintype "passive"))
      (node (ref "X4") (pin "1") (pinfunction "KL_1") (pintype "passive"))
    )
    (net (code "140") (name "Net-(X4B-KL)") (class "Default")
      (node (ref "BR1") (pin "AC2") (pinfunction "AC2_AC2") (pintype "passive"))
      (node (ref "X4") (pin "2") (pinfunction "KL_2") (pintype "passive"))
    )
    (net (code "141") (name "Net-(X5A-KL)") (class "Default")
      (node (ref "BR3") (pin "AC1") (pinfunction "AC1_AC1") (pintype "passive"))
      (node (ref "X5") (pin "1") (pinfunction "KL_1") (pintype "passive"))
    )
    (net (code "142") (name "Net-(X5B-KL)") (class "Default")
      (node (ref "BR3") (pin "AC2") (pinfunction "AC2_AC2") (pintype "passive"))
      (node (ref "X5") (pin "2") (pinfunction "KL_2") (pintype "passive"))
    )
    (net (code "143") (name "V+") (class "Default")
      (node (ref "BR2") (pin "+") (pinfunction "+_+") (pintype "passive"))
      (node (ref "C16") (pin "+") (pinfunction "+_+") (pintype "passive"))
      (node (ref "R26") (pin "2") (pinfunction "2_2") (pintype "passive"))
      (node (ref "REG1") (pin "1") (pinfunction "VIN_1") (pintype "input"))
    )
    (net (code "144") (name "VCC") (class "Default")
      (node (ref "BR3") (pin "+") (pinfunction "+_+") (pintype "passive"))
      (node (ref "C66") (pin "+") (pinfunction "+_+") (pintype "passive"))
      (node (ref "REG5") (pin "1") (pinfunction "VIN_1") (pintype "input"))
      (node (ref "REG6") (pin "3") (pinfunction "IN_3") (pintype "input"))
      (node (ref "REG7") (pin "3") (pinfunction "IN_3") (pintype "input"))
    )
    (net (code "145") (name "unconnected-(CON1-Pad4)") (class "Default")
      (node (ref "CON1") (pin "4") (pinfunction "4_4") (pintype "passive"))
    )
    (net (code "146") (name "unconnected-(CON2-Pad4)") (class "Default")
      (node (ref "CON2") (pin "4") (pinfunction "4_4") (pintype "passive"))
    )
    (net (code "147") (name "unconnected-(REF1-NC-Pad3)") (class "Default")
      (node (ref "REF1") (pin "3") (pinfunction "NC_3") (pintype "no_connect"))
    )
    (net (code "148") (name "unconnected-(REF2-NC-Pad3)") (class "Default")
      (node (ref "REF2") (pin "3") (pinfunction "NC_3") (pintype "no_connect"))
    )
    (net (code "149") (name "unconnected-(REF3-NC-Pad3)") (class "Default")
      (node (ref "REF3") (pin "3") (pinfunction "NC_3") (pintype "no_connect"))
    )
    (net (code "150") (name "unconnected-(REF4-NC-Pad3)") (class "Default")
      (node (ref "REF4") (pin "3") (pinfunction "NC_3") (pintype "no_connect"))
    )
    (net (code "151") (name "unconnected-(REF5-NC-Pad3)") (class "Default")
      (node (ref "REF5") (pin "3") (pinfunction "NC_3") (pintype "no_connect"))
    )
    (net (code "152") (name "unconnected-(REF6-NC-Pad3)") (class "Default")
      (node (ref "REF6") (pin "3") (pinfunction "NC_3") (pintype "no_connect"))
    )
    (net (code "153") (name "unconnected-(U4A-OUT-Pad1)") (class "Default")
      (node (ref "U4") (pin "1") (pinfunction "OUT_1") (pintype "output"))
    )
    (net (code "154") (name "unconnected-(U5A-OUT-Pad1)") (class "Default")
      (node (ref "U5") (pin "1") (pinfunction "OUT_1") (pintype "output"))
    )
    (net (code "155") (name "unconnected-(U6-ADR1-Pad10)") (class "Default")
      (node (ref "U6") (pin "10") (pinfunction "ADR1_10") (pintype "input"))
    )
    (net (code "156") (name "unconnected-(U6-CH1+-Pad1)") (class "Default")
      (node (ref "U6") (pin "1") (pinfunction "CH1+_1") (pintype "input"))
    )
    (net (code "157") (name "unconnected-(U7-VOUTC-Pad7)") (class "Default")
      (node (ref "U7") (pin "7") (pinfunction "VOUTC_7") (pintype "output"))
    )
    (net (code "158") (name "unconnected-(U7-VOUTD-Pad8)") (class "Default")
      (node (ref "U7") (pin "8") (pinfunction "VOUTD_8") (pintype "output"))
    )
    (net (code "159") (name "unconnected-(U8-ADR0-Pad9)") (class "Default")
      (node (ref "U8") (pin "9") (pinfunction "ADR0_9") (pintype "input"))
    )
    (net (code "160") (name "unconnected-(U8-CH1+-Pad1)") (class "Default")
      (node (ref "U8") (pin "1") (pinfunction "CH1+_1") (pintype "input"))
    )
    (net (code "161") (name "unconnected-(U9-VOUTC-Pad7)") (class "Default")
      (node (ref "U9") (pin "7") (pinfunction "VOUTC_7") (pintype "output"))
    )
    (net (code "162") (name "unconnected-(U9-VOUTD-Pad8)") (class "Default")
      (node (ref "U9") (pin "8") (pinfunction "VOUTD_8") (pintype "output"))
    )
    (net (code "163") (name "unconnected-(U10-ADIN-Pad4)") (class "Default")
      (node (ref "U10") (pin "4") (pinfunction "ADIN_4") (pintype "bidirectional"))
    )
    (net (code "164") (name "unconnected-(U10-BDOUT-Pad13)") (class "Default")
      (node (ref "U10") (pin "13") (pinfunction "BDOUT_13") (pintype "bidirectional"))
    )
    (net (code "165") (name "unconnected-(U10-NC1-Pad2)") (class "Default")
      (node (ref "U10") (pin "2") (pinfunction "NC1_2") (pintype "no_connect"))
    )
    (net (code "166") (name "unconnected-(U10-NC_1-Pad7)") (class "Default")
      (node (ref "U10") (pin "7") (pinfunction "NC_1_7") (pintype "no_connect"))
    )
    (net (code "167") (name "unconnected-(U10-NC_7-Pad10)") (class "Default")
      (node (ref "U10") (pin "10") (pinfunction "NC_7_10") (pintype "no_connect"))
    )
    (net (code "168") (name "unconnected-(U10-NC_8-Pad15)") (class "Default")
      (node (ref "U10") (pin "15") (pinfunction "NC_8_15") (pintype "no_connect"))
    )
    (net (code "169") (name "unconnected-(U11-ADIN-Pad4)") (class "Default")
      (node (ref "U11") (pin "4") (pinfunction "ADIN_4") (pintype "bidirectional"))
    )
    (net (code "170") (name "unconnected-(U11-BDOUT-Pad13)") (class "Default")
      (node (ref "U11") (pin "13") (pinfunction "BDOUT_13") (pintype "bidirectional"))
    )
    (net (code "171") (name "unconnected-(U11-NC1-Pad2)") (class "Default")
      (node (ref "U11") (pin "2") (pinfunction "NC1_2") (pintype "no_connect"))
    )
    (net (code "172") (name "unconnected-(U11-NC_1-Pad7)") (class "Default")
      (node (ref "U11") (pin "7") (pinfunction "NC_1_7") (pintype "no_connect"))
    )
    (net (code "173") (name "unconnected-(U11-NC_7-Pad10)") (class "Default")
      (node (ref "U11") (pin "10") (pinfunction "NC_7_10") (pintype "no_connect"))
    )
    (net (code "174") (name "unconnected-(U11-NC_8-Pad15)") (class "Default")
      (node (ref "U11") (pin "15") (pinfunction "NC_8_15") (pintype "no_connect"))
    )
    (net (code "175") (name "unconnected-(U12-(PCINT8{slash}ADC0)PC0-Pad23)") (class "Default")
      (node (ref "U12") (pin "23") (pinfunction "(PCINT8/ADC0)PC0_23") (pintype "bidirectional"))
    )
    (net (code "176") (name "unconnected-(U12-(PCINT9{slash}ADC1)PC1-Pad24)") (class "Default")
      (node (ref "U12") (pin "24") (pinfunction "(PCINT9/ADC1)PC1_24") (pintype "bidirectional"))
    )
    (net (code "177") (name "unconnected-(U12-ADC6-Pad19)") (class "Default")
      (node (ref "U12") (pin "19") (pinfunction "ADC6_19") (pintype "bidirectional"))
    )
    (net (code "178") (name "unconnected-(U12-ADC7-Pad22)") (class "Default")
      (node (ref "U12") (pin "22") (pinfunction "ADC7_22") (pintype "bidirectional"))
    )
  )
)
